# UMN_HASP_2015_HVPS.net
KiCad netlist of a schematic drawn in EAGLE
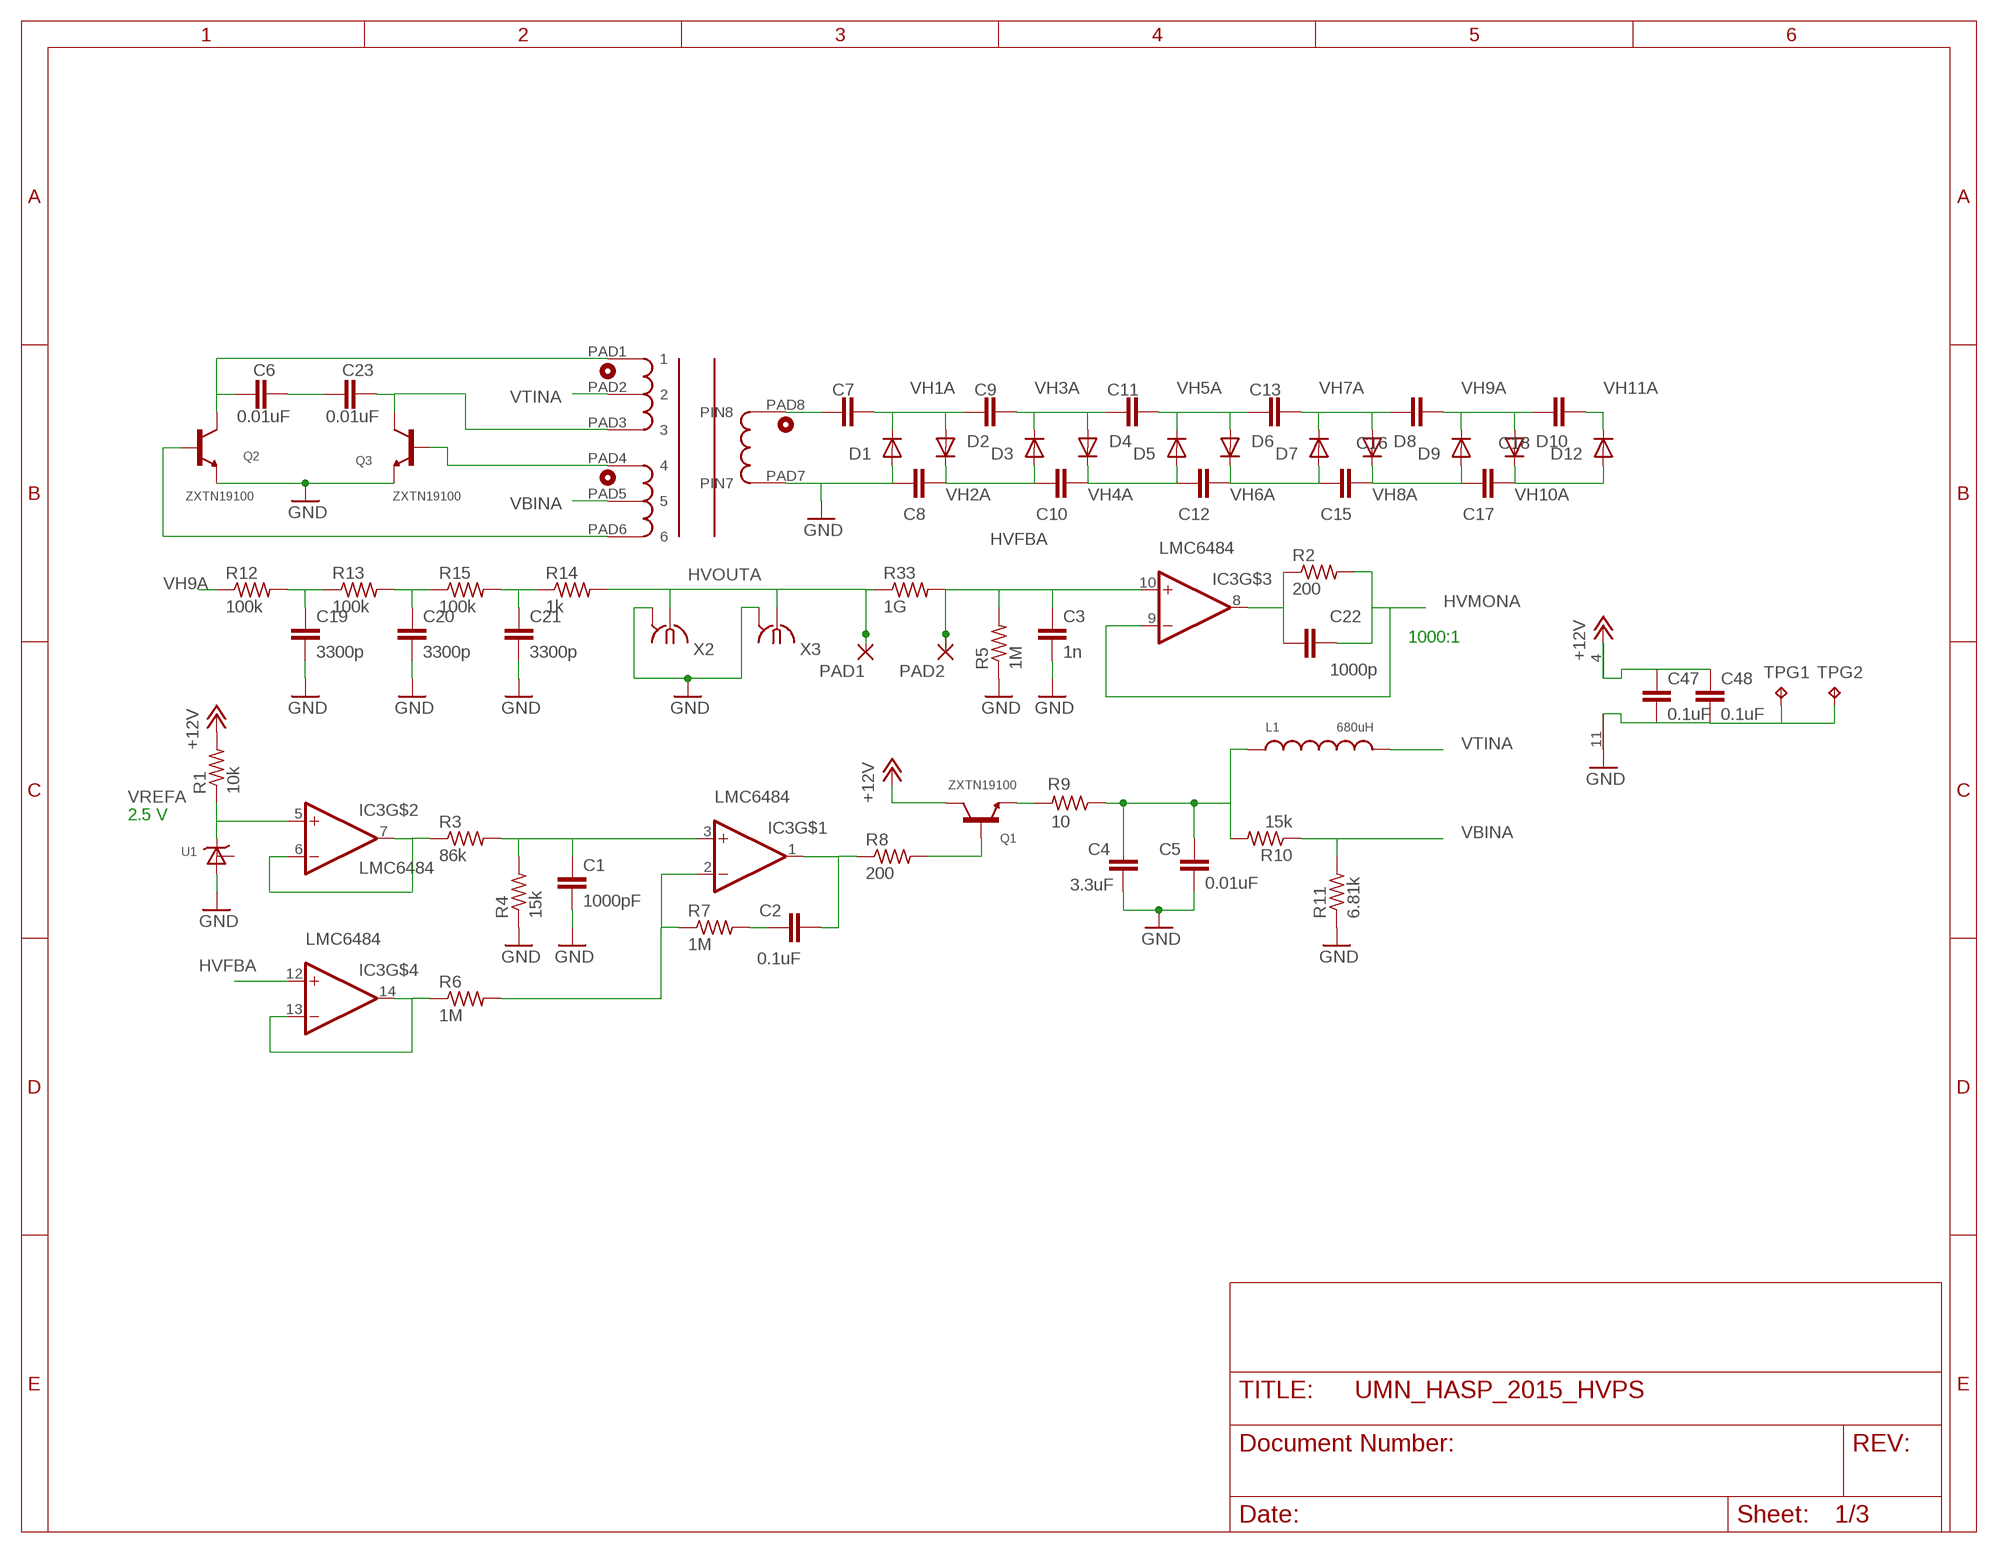
[diagram p0: schematic, sheet 1]
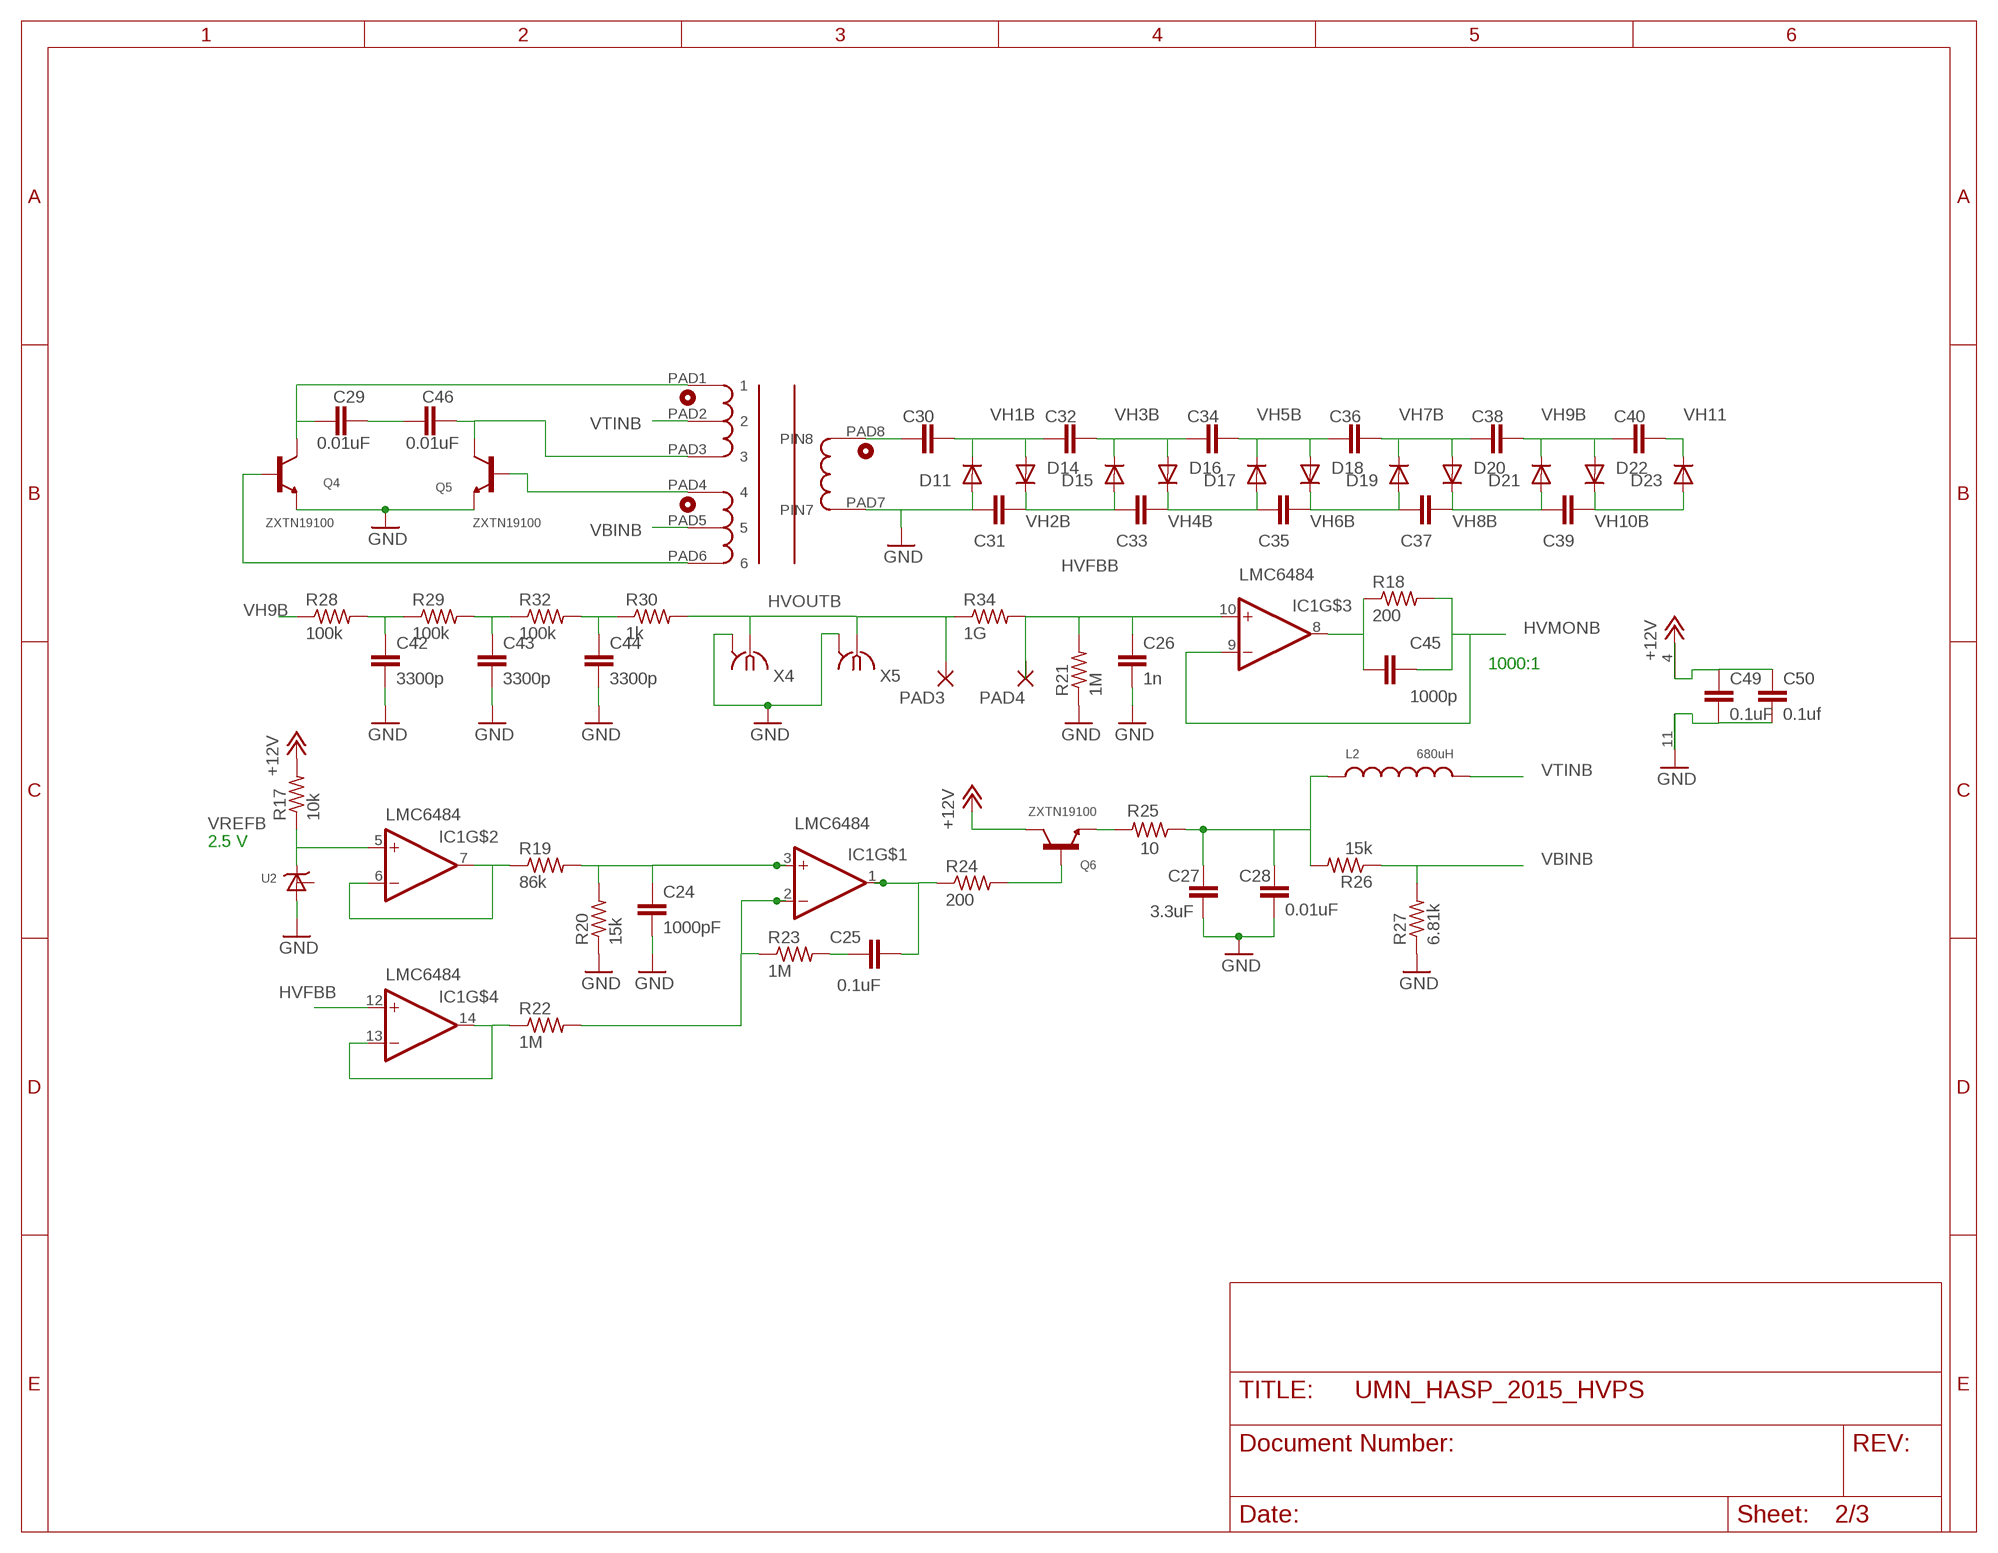
[diagram p1: schematic, sheet 2]
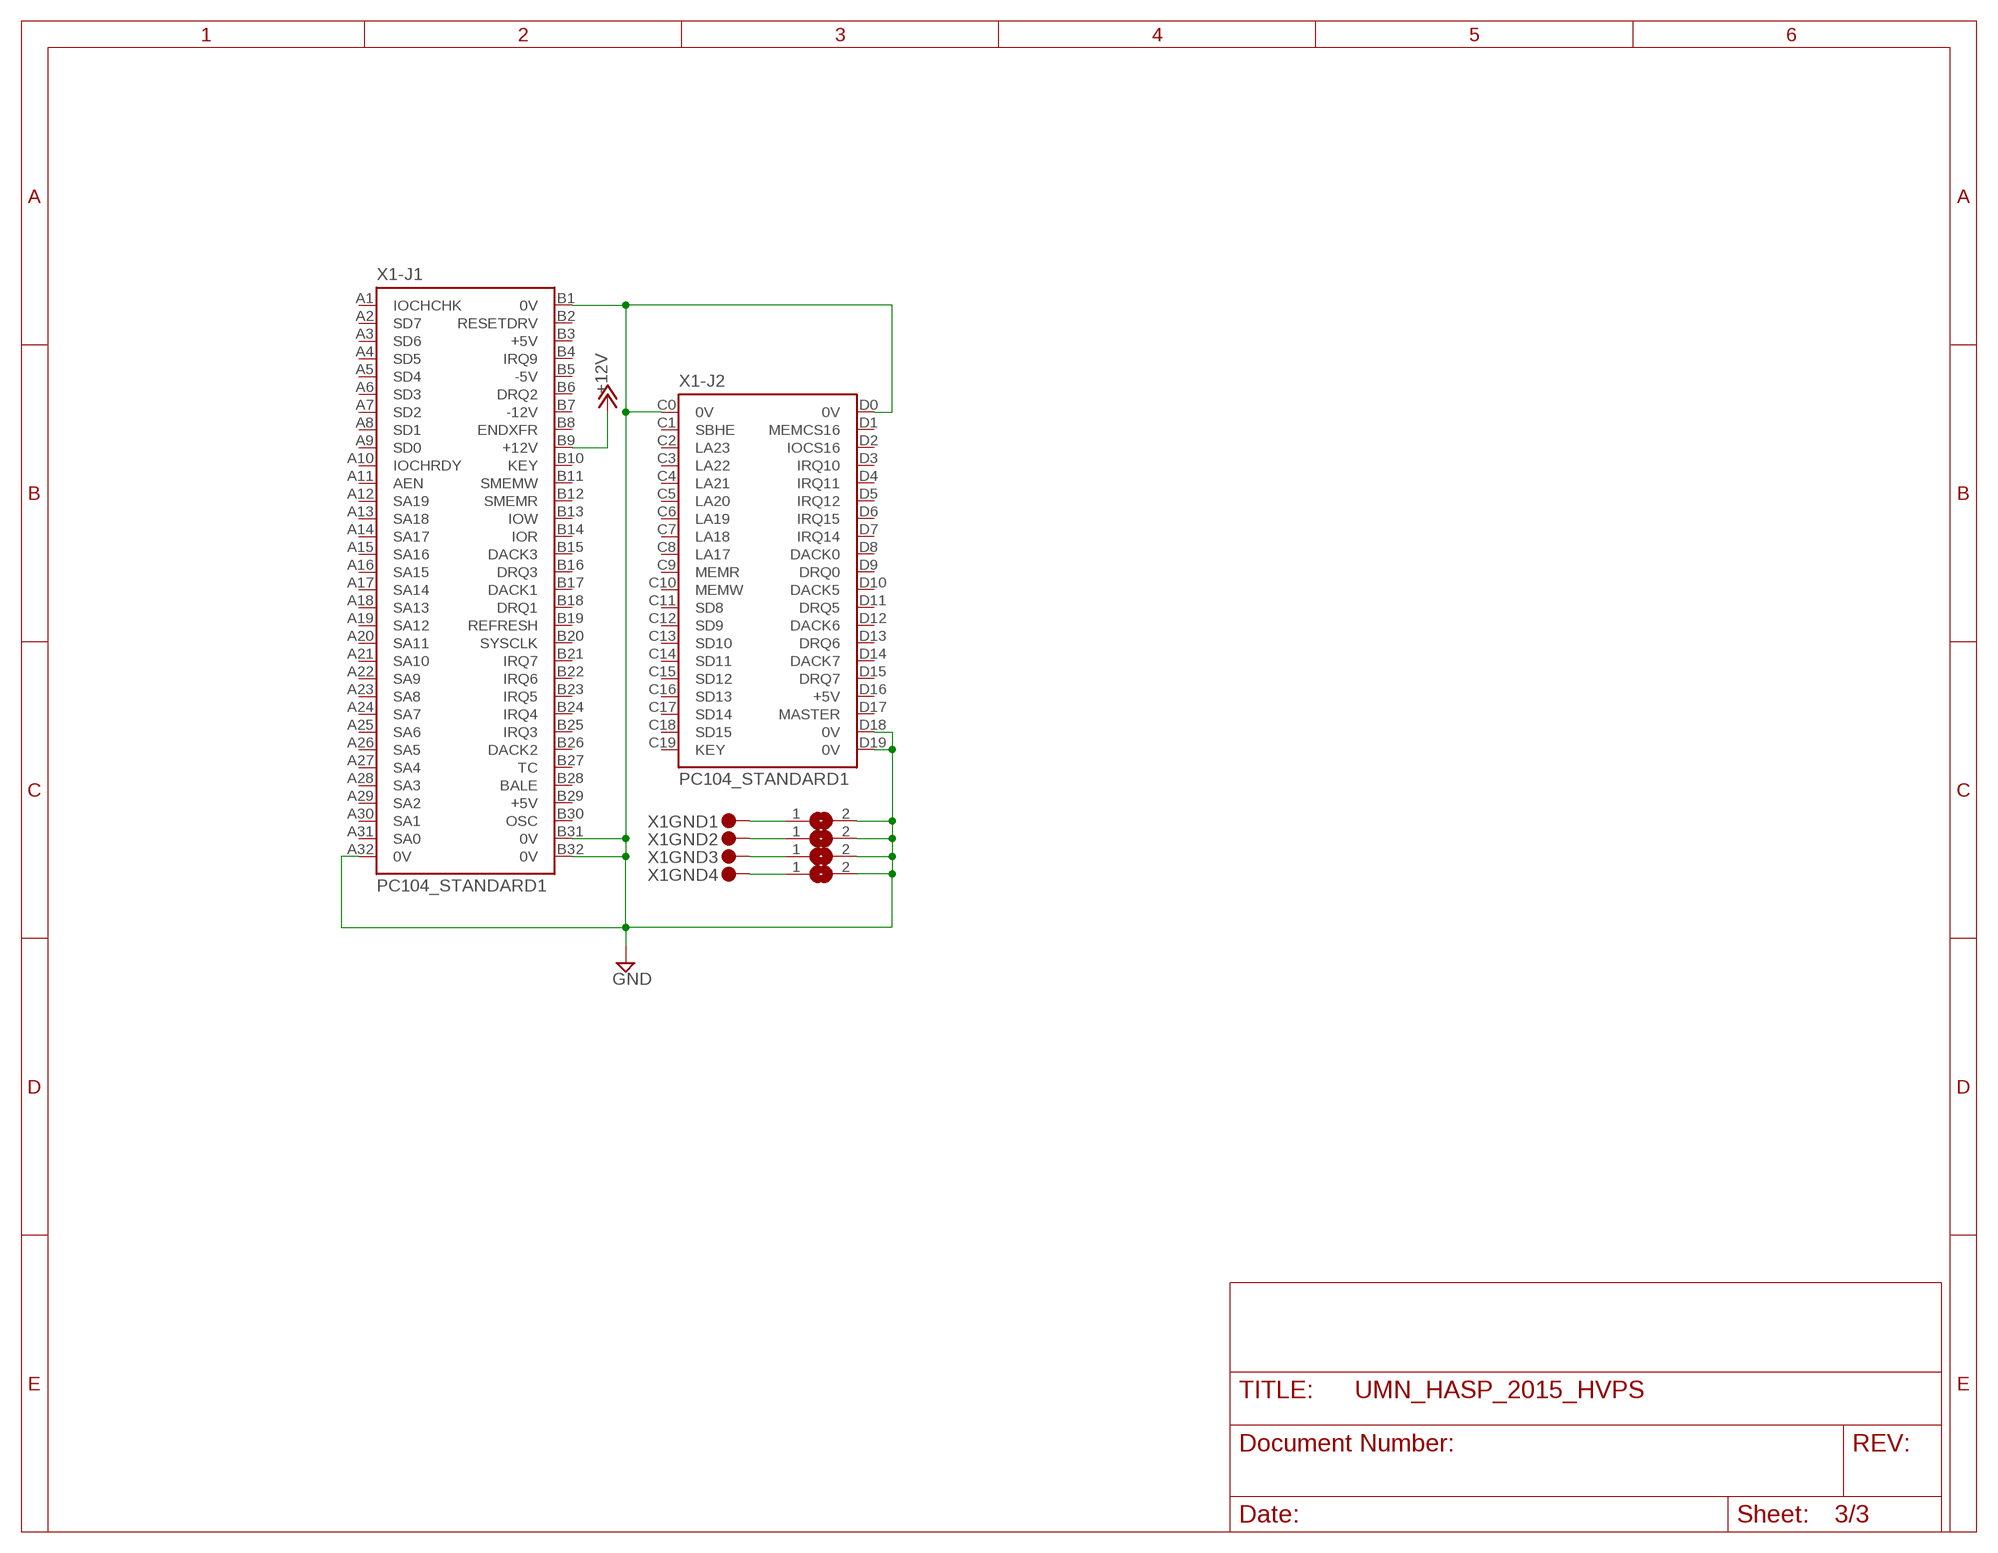
[diagram p2: schematic, sheet 3]

(export (version "E")
  (design (tool "Eeschema 10.0.6"))
  (components
    (comp (ref "SJ1") (value "SJ") (footprint "eagle-import:SJ") (libsource (lib "eagle-import") (part "SJ")))
    (comp (ref "SJ2") (value "SJ") (footprint "eagle-import:SJ") (libsource (lib "eagle-import") (part "SJ")))
    (comp (ref "SJ3") (value "SJ") (footprint "eagle-import:SJ") (libsource (lib "eagle-import") (part "SJ")))
    (comp (ref "SJ4") (value "SJ") (footprint "eagle-import:SJ") (libsource (lib "eagle-import") (part "SJ")))
    (comp (ref "X1")
      (value "PC104_STANDARD1")
      (footprint "eagle-import:PC104-STANDARD")
      (libsource (lib "eagle-import") (part "PC104_STANDARD1"))
    )
    (comp (ref "C1")
      (value "1000pF")
      (footprint "eagle-import:C0603")
      (libsource (lib "eagle-import") (part "C-EUC0603"))
    )
    (comp (ref "C2")
      (value "0.1uF")
      (footprint "eagle-import:C0603")
      (libsource (lib "eagle-import") (part "C-EUC0603"))
    )
    (comp (ref "C3")
      (value "1n")
      (footprint "eagle-import:C0603")
      (libsource (lib "eagle-import") (part "C-EUC0603"))
    )
    (comp (ref "C4")
      (value "3.3uF")
      (footprint "eagle-import:C0603")
      (libsource (lib "eagle-import") (part "C-EUC0603"))
    )
    (comp (ref "C5")
      (value "0.01uF")
      (footprint "eagle-import:C0603")
      (libsource (lib "eagle-import") (part "C-EUC0603"))
    )
    (comp (ref "C6")
      (value "0.01uF")
      (footprint "eagle-import:C0603")
      (libsource (lib "eagle-import") (part "C-EUC0603"))
    )
    (comp (ref "C7")
      (value "C-EUC1206K")
      (footprint "eagle-import:C1206K")
      (libsource (lib "eagle-import") (part "C-EUC1206K"))
    )
    (comp (ref "C8")
      (value "C-EUC1206K")
      (footprint "eagle-import:C1206K")
      (libsource (lib "eagle-import") (part "C-EUC1206K"))
    )
    (comp (ref "C9")
      (value "C-EUC1206K")
      (footprint "eagle-import:C1206K")
      (libsource (lib "eagle-import") (part "C-EUC1206K"))
    )
    (comp (ref "C10")
      (value "C-EUC1206K")
      (footprint "eagle-import:C1206K")
      (libsource (lib "eagle-import") (part "C-EUC1206K"))
    )
    (comp (ref "C11")
      (value "C-EUC1206K")
      (footprint "eagle-import:C1206K")
      (libsource (lib "eagle-import") (part "C-EUC1206K"))
    )
    (comp (ref "C12")
      (value "C-EUC1206K")
      (footprint "eagle-import:C1206K")
      (libsource (lib "eagle-import") (part "C-EUC1206K"))
    )
    (comp (ref "C13")
      (value "C-EUC1206K")
      (footprint "eagle-import:C1206K")
      (libsource (lib "eagle-import") (part "C-EUC1206K"))
    )
    (comp (ref "C15")
      (value "C-EUC1206K")
      (footprint "eagle-import:C1206K")
      (libsource (lib "eagle-import") (part "C-EUC1206K"))
    )
    (comp (ref "C16")
      (value "C-EUC1206K")
      (footprint "eagle-import:C1206K")
      (libsource (lib "eagle-import") (part "C-EUC1206K"))
    )
    (comp (ref "C17")
      (value "C-EUC1206K")
      (footprint "eagle-import:C1206K")
      (libsource (lib "eagle-import") (part "C-EUC1206K"))
    )
    (comp (ref "C18")
      (value "C-EUC1206K")
      (footprint "eagle-import:C1206K")
      (libsource (lib "eagle-import") (part "C-EUC1206K"))
    )
    (comp (ref "C19")
      (value "3300p")
      (footprint "eagle-import:C1206")
      (libsource (lib "eagle-import") (part "C-EUC1206"))
    )
    (comp (ref "C20")
      (value "3300p")
      (footprint "eagle-import:C1206")
      (libsource (lib "eagle-import") (part "C-EUC1206"))
    )
    (comp (ref "C21")
      (value "3300p")
      (footprint "eagle-import:C1206")
      (libsource (lib "eagle-import") (part "C-EUC1206"))
    )
    (comp (ref "C22")
      (value "1000p")
      (footprint "eagle-import:C0603")
      (libsource (lib "eagle-import") (part "C-EUC0603"))
    )
    (comp (ref "C23")
      (value "0.01uF")
      (footprint "eagle-import:C0603")
      (libsource (lib "eagle-import") (part "C-EUC0603"))
    )
    (comp (ref "C47")
      (value "0.1uF")
      (footprint "eagle-import:C0603")
      (libsource (lib "eagle-import") (part "C-EUC0603"))
    )
    (comp (ref "C48")
      (value "0.1uF")
      (footprint "eagle-import:C0603")
      (libsource (lib "eagle-import") (part "C-EUC0603"))
    )
    (comp (ref "D1")
      (value "DIODE-DO-214AC")
      (footprint "eagle-import:DO-214AC")
      (libsource (lib "eagle-import") (part "DIODE-DO-214AC"))
    )
    (comp (ref "D2")
      (value "DIODE-DO-214AC")
      (footprint "eagle-import:DO-214AC")
      (libsource (lib "eagle-import") (part "DIODE-DO-214AC"))
    )
    (comp (ref "D3")
      (value "DIODE-DO-214AC")
      (footprint "eagle-import:DO-214AC")
      (libsource (lib "eagle-import") (part "DIODE-DO-214AC"))
    )
    (comp (ref "D4")
      (value "DIODE-DO-214AC")
      (footprint "eagle-import:DO-214AC")
      (libsource (lib "eagle-import") (part "DIODE-DO-214AC"))
    )
    (comp (ref "D5")
      (value "DIODE-DO-214AC")
      (footprint "eagle-import:DO-214AC")
      (libsource (lib "eagle-import") (part "DIODE-DO-214AC"))
    )
    (comp (ref "D6")
      (value "DIODE-DO-214AC")
      (footprint "eagle-import:DO-214AC")
      (libsource (lib "eagle-import") (part "DIODE-DO-214AC"))
    )
    (comp (ref "D7")
      (value "DIODE-DO-214AC")
      (footprint "eagle-import:DO-214AC")
      (libsource (lib "eagle-import") (part "DIODE-DO-214AC"))
    )
    (comp (ref "D8")
      (value "DIODE-DO-214AC")
      (footprint "eagle-import:DO-214AC")
      (libsource (lib "eagle-import") (part "DIODE-DO-214AC"))
    )
    (comp (ref "D9")
      (value "DIODE-DO-214AC")
      (footprint "eagle-import:DO-214AC")
      (libsource (lib "eagle-import") (part "DIODE-DO-214AC"))
    )
    (comp (ref "D10")
      (value "DIODE-DO-214AC")
      (footprint "eagle-import:DO-214AC")
      (libsource (lib "eagle-import") (part "DIODE-DO-214AC"))
    )
    (comp (ref "D12")
      (value "DIODE-DO-214AC")
      (footprint "eagle-import:DO-214AC")
      (libsource (lib "eagle-import") (part "DIODE-DO-214AC"))
    )
    (comp (ref "IC3")
      (value "LMC6484")
      (footprint "eagle-import:SO14")
      (libsource (lib "eagle-import") (part "LMC6484"))
    )
    (comp (ref "L1")
      (value "680uH")
      (footprint "eagle-import:INDUCTOR_SRR1280BOURNS")
      (libsource (lib "eagle-import") (part "INDUCTOR_BOURNS_SRR1280_SERIES"))
    )
    (comp (ref "PAD1")
      (value "WIREPADSMD1,27-254")
      (footprint "eagle-import:SMD1,27-2,54")
      (libsource (lib "eagle-import") (part "WIREPADSMD1,27-254"))
    )
    (comp (ref "PAD2")
      (value "WIREPADSMD1,27-254")
      (footprint "eagle-import:SMD1,27-2,54")
      (libsource (lib "eagle-import") (part "WIREPADSMD1,27-254"))
    )
    (comp (ref "Q1")
      (value "ZXTN19100")
      (footprint "eagle-import:SOT23_2CM_SQ_AREA")
      (libsource (lib "eagle-import") (part "ZXTN19100_NPN"))
    )
    (comp (ref "Q2")
      (value "ZXTN19100")
      (footprint "eagle-import:SOT23_2CM_SQ_AREA")
      (libsource (lib "eagle-import") (part "ZXTN19100_NPN"))
    )
    (comp (ref "Q3")
      (value "ZXTN19100")
      (footprint "eagle-import:SOT23_2CM_SQ_AREA")
      (libsource (lib "eagle-import") (part "ZXTN19100_NPN"))
    )
    (comp (ref "R1")
      (value "10k")
      (footprint "eagle-import:R0603")
      (libsource (lib "eagle-import") (part "R-US_R0603"))
    )
    (comp (ref "R2")
      (value "200")
      (footprint "eagle-import:R0603")
      (libsource (lib "eagle-import") (part "R-US_R0603"))
    )
    (comp (ref "R3")
      (value "86k")
      (footprint "eagle-import:R0603")
      (libsource (lib "eagle-import") (part "R-US_R0603"))
    )
    (comp (ref "R4")
      (value "15k")
      (footprint "eagle-import:R0603")
      (libsource (lib "eagle-import") (part "R-US_R0603"))
    )
    (comp (ref "R5")
      (value "1M")
      (footprint "eagle-import:R0603")
      (libsource (lib "eagle-import") (part "R-US_R0603"))
    )
    (comp (ref "R6")
      (value "1M")
      (footprint "eagle-import:R0603")
      (libsource (lib "eagle-import") (part "R-US_R0603"))
    )
    (comp (ref "R7")
      (value "1M")
      (footprint "eagle-import:R0603")
      (libsource (lib "eagle-import") (part "R-US_R0603"))
    )
    (comp (ref "R8")
      (value "200")
      (footprint "eagle-import:R0603")
      (libsource (lib "eagle-import") (part "R-US_R0603"))
    )
    (comp (ref "R9")
      (value "10")
      (footprint "eagle-import:R2010")
      (libsource (lib "eagle-import") (part "R-US_R2010"))
    )
    (comp (ref "R10")
      (value "15k")
      (footprint "eagle-import:R0603")
      (libsource (lib "eagle-import") (part "R-US_R0603"))
    )
    (comp (ref "R11")
      (value "6.81k")
      (footprint "eagle-import:R0603")
      (libsource (lib "eagle-import") (part "R-US_R0603"))
    )
    (comp (ref "R12")
      (value "100k")
      (footprint "eagle-import:R0603")
      (libsource (lib "eagle-import") (part "R-US_R0603"))
    )
    (comp (ref "R13")
      (value "100k")
      (footprint "eagle-import:R0603")
      (libsource (lib "eagle-import") (part "R-US_R0603"))
    )
    (comp (ref "R14")
      (value "1k")
      (footprint "eagle-import:R0603")
      (libsource (lib "eagle-import") (part "R-US_R0603"))
    )
    (comp (ref "R15")
      (value "100k")
      (footprint "eagle-import:R0603")
      (libsource (lib "eagle-import") (part "R-US_R0603"))
    )
    (comp (ref "R33")
      (value "1G")
      (footprint "eagle-import:R2512")
      (libsource (lib "eagle-import") (part "R-US_R2512"))
    )
    (comp (ref "TPG1")
      (value "TPB1,27")
      (footprint "eagle-import:B1,27")
      (libsource (lib "eagle-import") (part "TPB1,27"))
    )
    (comp (ref "TPG2")
      (value "TPB1,27")
      (footprint "eagle-import:B1,27")
      (libsource (lib "eagle-import") (part "TPB1,27"))
    )
    (comp (ref "U$1")
      (value "TDK_TRANSFORMER_RM6_CORE")
      (footprint "eagle-import:SM_DCOILFORMER_RM6")
      (libsource (lib "eagle-import") (part "TDK_TRANSFORMER_RM6_CORE"))
    )
    (comp (ref "U1")
      (value "ADR525")
      (footprint "eagle-import:SOT23A")
      (libsource (lib "eagle-import") (part "ADR525"))
    )
    (comp (ref "X2")
      (value "BU-SMA-V-REVB")
      (footprint "eagle-import:BU-SMA-V")
      (libsource (lib "eagle-import") (part "BU-SMA-V-REVB"))
    )
    (comp (ref "X3")
      (value "BU-SMA-V-REVB")
      (footprint "eagle-import:BU-SMA-V")
      (libsource (lib "eagle-import") (part "BU-SMA-V-REVB"))
    )
    (comp (ref "C24")
      (value "1000pF")
      (footprint "eagle-import:C0603")
      (libsource (lib "eagle-import") (part "C-EUC0603"))
    )
    (comp (ref "C25")
      (value "0.1uF")
      (footprint "eagle-import:C0603")
      (libsource (lib "eagle-import") (part "C-EUC0603"))
    )
    (comp (ref "C26")
      (value "1n")
      (footprint "eagle-import:C0603")
      (libsource (lib "eagle-import") (part "C-EUC0603"))
    )
    (comp (ref "C27")
      (value "3.3uF")
      (footprint "eagle-import:C0603")
      (libsource (lib "eagle-import") (part "C-EUC0603"))
    )
    (comp (ref "C28")
      (value "0.01uF")
      (footprint "eagle-import:C0603")
      (libsource (lib "eagle-import") (part "C-EUC0603"))
    )
    (comp (ref "C29")
      (value "0.01uF")
      (footprint "eagle-import:C0603")
      (libsource (lib "eagle-import") (part "C-EUC0603"))
    )
    (comp (ref "C30")
      (value "C-EUC1206K")
      (footprint "eagle-import:C1206K")
      (libsource (lib "eagle-import") (part "C-EUC1206K"))
    )
    (comp (ref "C31")
      (value "C-EUC1206K")
      (footprint "eagle-import:C1206K")
      (libsource (lib "eagle-import") (part "C-EUC1206K"))
    )
    (comp (ref "C32")
      (value "C-EUC1206K")
      (footprint "eagle-import:C1206K")
      (libsource (lib "eagle-import") (part "C-EUC1206K"))
    )
    (comp (ref "C33")
      (value "C-EUC1206K")
      (footprint "eagle-import:C1206K")
      (libsource (lib "eagle-import") (part "C-EUC1206K"))
    )
    (comp (ref "C34")
      (value "C-EUC1206K")
      (footprint "eagle-import:C1206K")
      (libsource (lib "eagle-import") (part "C-EUC1206K"))
    )
    (comp (ref "C35")
      (value "C-EUC1206K")
      (footprint "eagle-import:C1206K")
      (libsource (lib "eagle-import") (part "C-EUC1206K"))
    )
    (comp (ref "C36")
      (value "C-EUC1206K")
      (footprint "eagle-import:C1206K")
      (libsource (lib "eagle-import") (part "C-EUC1206K"))
    )
    (comp (ref "C37")
      (value "C-EUC1206K")
      (footprint "eagle-import:C1206K")
      (libsource (lib "eagle-import") (part "C-EUC1206K"))
    )
    (comp (ref "C38")
      (value "C-EUC1206K")
      (footprint "eagle-import:C1206K")
      (libsource (lib "eagle-import") (part "C-EUC1206K"))
    )
    (comp (ref "C39")
      (value "C-EUC1206K")
      (footprint "eagle-import:C1206K")
      (libsource (lib "eagle-import") (part "C-EUC1206K"))
    )
    (comp (ref "C40")
      (value "C-EUC1206K")
      (footprint "eagle-import:C1206K")
      (libsource (lib "eagle-import") (part "C-EUC1206K"))
    )
    (comp (ref "C42")
      (value "3300p")
      (footprint "eagle-import:C1206")
      (libsource (lib "eagle-import") (part "C-EUC1206"))
    )
    (comp (ref "C43")
      (value "3300p")
      (footprint "eagle-import:C1206")
      (libsource (lib "eagle-import") (part "C-EUC1206"))
    )
    (comp (ref "C44")
      (value "3300p")
      (footprint "eagle-import:C1206")
      (libsource (lib "eagle-import") (part "C-EUC1206"))
    )
    (comp (ref "C45")
      (value "1000p")
      (footprint "eagle-import:C0603")
      (libsource (lib "eagle-import") (part "C-EUC0603"))
    )
    (comp (ref "C46")
      (value "0.01uF")
      (footprint "eagle-import:C0603")
      (libsource (lib "eagle-import") (part "C-EUC0603"))
    )
    (comp (ref "C49")
      (value "0.1uF")
      (footprint "eagle-import:C0603")
      (libsource (lib "eagle-import") (part "C-EUC0603"))
    )
    (comp (ref "C50")
      (value "0.1uf")
      (footprint "eagle-import:C0603")
      (libsource (lib "eagle-import") (part "C-EUC0603"))
    )
    (comp (ref "D11")
      (value "DIODE-DO-214AC")
      (footprint "eagle-import:DO-214AC")
      (libsource (lib "eagle-import") (part "DIODE-DO-214AC"))
    )
    (comp (ref "D14")
      (value "DIODE-DO-214AC")
      (footprint "eagle-import:DO-214AC")
      (libsource (lib "eagle-import") (part "DIODE-DO-214AC"))
    )
    (comp (ref "D15")
      (value "DIODE-DO-214AC")
      (footprint "eagle-import:DO-214AC")
      (libsource (lib "eagle-import") (part "DIODE-DO-214AC"))
    )
    (comp (ref "D16")
      (value "DIODE-DO-214AC")
      (footprint "eagle-import:DO-214AC")
      (libsource (lib "eagle-import") (part "DIODE-DO-214AC"))
    )
    (comp (ref "D17")
      (value "DIODE-DO-214AC")
      (footprint "eagle-import:DO-214AC")
      (libsource (lib "eagle-import") (part "DIODE-DO-214AC"))
    )
    (comp (ref "D18")
      (value "DIODE-DO-214AC")
      (footprint "eagle-import:DO-214AC")
      (libsource (lib "eagle-import") (part "DIODE-DO-214AC"))
    )
    (comp (ref "D19")
      (value "DIODE-DO-214AC")
      (footprint "eagle-import:DO-214AC")
      (libsource (lib "eagle-import") (part "DIODE-DO-214AC"))
    )
    (comp (ref "D20")
      (value "DIODE-DO-214AC")
      (footprint "eagle-import:DO-214AC")
      (libsource (lib "eagle-import") (part "DIODE-DO-214AC"))
    )
    (comp (ref "D21")
      (value "DIODE-DO-214AC")
      (footprint "eagle-import:DO-214AC")
      (libsource (lib "eagle-import") (part "DIODE-DO-214AC"))
    )
    (comp (ref "D22")
      (value "DIODE-DO-214AC")
      (footprint "eagle-import:DO-214AC")
      (libsource (lib "eagle-import") (part "DIODE-DO-214AC"))
    )
    (comp (ref "D23")
      (value "DIODE-DO-214AC")
      (footprint "eagle-import:DO-214AC")
      (libsource (lib "eagle-import") (part "DIODE-DO-214AC"))
    )
    (comp (ref "IC1")
      (value "LMC6484")
      (footprint "eagle-import:SO14")
      (libsource (lib "eagle-import") (part "LMC6484"))
    )
    (comp (ref "L2")
      (value "680uH")
      (footprint "eagle-import:INDUCTOR_SRR1280BOURNS")
      (libsource (lib "eagle-import") (part "INDUCTOR_BOURNS_SRR1280_SERIES"))
    )
    (comp (ref "PAD3")
      (value "WIREPADSMD1,27-254")
      (footprint "eagle-import:SMD1,27-2,54")
      (libsource (lib "eagle-import") (part "WIREPADSMD1,27-254"))
    )
    (comp (ref "PAD4")
      (value "WIREPADSMD1,27-254")
      (footprint "eagle-import:SMD1,27-2,54")
      (libsource (lib "eagle-import") (part "WIREPADSMD1,27-254"))
    )
    (comp (ref "Q4")
      (value "ZXTN19100")
      (footprint "eagle-import:SOT23_2CM_SQ_AREA")
      (libsource (lib "eagle-import") (part "ZXTN19100_NPN"))
    )
    (comp (ref "Q5")
      (value "ZXTN19100")
      (footprint "eagle-import:SOT23_2CM_SQ_AREA")
      (libsource (lib "eagle-import") (part "ZXTN19100_NPN"))
    )
    (comp (ref "Q6")
      (value "ZXTN19100")
      (footprint "eagle-import:SOT23_2CM_SQ_AREA")
      (libsource (lib "eagle-import") (part "ZXTN19100_NPN"))
    )
    (comp (ref "R17")
      (value "10k")
      (footprint "eagle-import:R0603")
      (libsource (lib "eagle-import") (part "R-US_R0603"))
    )
    (comp (ref "R18")
      (value "200")
      (footprint "eagle-import:R0603")
      (libsource (lib "eagle-import") (part "R-US_R0603"))
    )
    (comp (ref "R19")
      (value "86k")
      (footprint "eagle-import:R0603")
      (libsource (lib "eagle-import") (part "R-US_R0603"))
    )
    (comp (ref "R20")
      (value "15k")
      (footprint "eagle-import:R0603")
      (libsource (lib "eagle-import") (part "R-US_R0603"))
    )
    (comp (ref "R21")
      (value "1M")
      (footprint "eagle-import:R0603")
      (libsource (lib "eagle-import") (part "R-US_R0603"))
    )
    (comp (ref "R22")
      (value "1M")
      (footprint "eagle-import:R0603")
      (libsource (lib "eagle-import") (part "R-US_R0603"))
    )
    (comp (ref "R23")
      (value "1M")
      (footprint "eagle-import:R0603")
      (libsource (lib "eagle-import") (part "R-US_R0603"))
    )
    (comp (ref "R24")
      (value "200")
      (footprint "eagle-import:R0603")
      (libsource (lib "eagle-import") (part "R-US_R0603"))
    )
    (comp (ref "R25")
      (value "10")
      (footprint "eagle-import:R2010")
      (libsource (lib "eagle-import") (part "R-US_R2010"))
    )
    (comp (ref "R26")
      (value "15k")
      (footprint "eagle-import:R0603")
      (libsource (lib "eagle-import") (part "R-US_R0603"))
    )
    (comp (ref "R27")
      (value "6.81k")
      (footprint "eagle-import:R0603")
      (libsource (lib "eagle-import") (part "R-US_R0603"))
    )
    (comp (ref "R28")
      (value "100k")
      (footprint "eagle-import:R0603")
      (libsource (lib "eagle-import") (part "R-US_R0603"))
    )
    (comp (ref "R29")
      (value "100k")
      (footprint "eagle-import:R0603")
      (libsource (lib "eagle-import") (part "R-US_R0603"))
    )
    (comp (ref "R30")
      (value "1k")
      (footprint "eagle-import:R0603")
      (libsource (lib "eagle-import") (part "R-US_R0603"))
    )
    (comp (ref "R32")
      (value "100k")
      (footprint "eagle-import:R0603")
      (libsource (lib "eagle-import") (part "R-US_R0603"))
    )
    (comp (ref "R34")
      (value "1G")
      (footprint "eagle-import:R2512")
      (libsource (lib "eagle-import") (part "R-US_R2512"))
    )
    (comp (ref "U$2")
      (value "TDK_TRANSFORMER_RM6_CORE")
      (footprint "eagle-import:SM_DCOILFORMER_RM6")
      (libsource (lib "eagle-import") (part "TDK_TRANSFORMER_RM6_CORE"))
    )
    (comp (ref "U2")
      (value "ADR525")
      (footprint "eagle-import:SOT23A")
      (libsource (lib "eagle-import") (part "ADR525"))
    )
    (comp (ref "X4")
      (value "BU-SMA-V-REVB")
      (footprint "eagle-import:BU-SMA-V")
      (libsource (lib "eagle-import") (part "BU-SMA-V-REVB"))
    )
    (comp (ref "X5")
      (value "BU-SMA-V-REVB")
      (footprint "eagle-import:BU-SMA-V")
      (libsource (lib "eagle-import") (part "BU-SMA-V-REVB"))
    )
  )
  (nets
    (net (code "1") (name "+12V") (class "Default")
      (node (ref "C47") (pin "1") (pinfunction "1_1") (pintype "passive"))
      (node (ref "C48") (pin "1") (pinfunction "1_1") (pintype "passive"))
      (node (ref "C49") (pin "1") (pinfunction "1_1") (pintype "passive"))
      (node (ref "C50") (pin "1") (pinfunction "1_1") (pintype "passive"))
      (node (ref "IC1") (pin "4") (pinfunction "V+_4") (pintype "power_in"))
      (node (ref "IC3") (pin "4") (pinfunction "V+_4") (pintype "power_in"))
      (node (ref "Q1") (pin "C") (pinfunction "C_C") (pintype "passive"))
      (node (ref "Q6") (pin "C") (pinfunction "C_C") (pintype "passive"))
      (node (ref "R1") (pin "2") (pinfunction "2_2") (pintype "passive"))
      (node (ref "R17") (pin "2") (pinfunction "2_2") (pintype "passive"))
      (node (ref "X1") (pin "B9") (pinfunction "+12V_B9") (pintype "passive"))
    )
    (net (code "2") (name "GND") (class "Default")
      (node (ref "C1") (pin "2") (pinfunction "2_2") (pintype "passive"))
      (node (ref "C19") (pin "2") (pinfunction "2_2") (pintype "passive"))
      (node (ref "C20") (pin "2") (pinfunction "2_2") (pintype "passive"))
      (node (ref "C21") (pin "2") (pinfunction "2_2") (pintype "passive"))
      (node (ref "C24") (pin "2") (pinfunction "2_2") (pintype "passive"))
      (node (ref "C26") (pin "2") (pinfunction "2_2") (pintype "passive"))
      (node (ref "C27") (pin "2") (pinfunction "2_2") (pintype "passive"))
      (node (ref "C28") (pin "2") (pinfunction "2_2") (pintype "passive"))
      (node (ref "C3") (pin "2") (pinfunction "2_2") (pintype "passive"))
      (node (ref "C31") (pin "1") (pinfunction "1_1") (pintype "passive"))
      (node (ref "C4") (pin "2") (pinfunction "2_2") (pintype "passive"))
      (node (ref "C42") (pin "2") (pinfunction "2_2") (pintype "passive"))
      (node (ref "C43") (pin "2") (pinfunction "2_2") (pintype "passive"))
      (node (ref "C44") (pin "2") (pinfunction "2_2") (pintype "passive"))
      (node (ref "C47") (pin "2") (pinfunction "2_2") (pintype "passive"))
      (node (ref "C48") (pin "2") (pinfunction "2_2") (pintype "passive"))
      (node (ref "C49") (pin "2") (pinfunction "2_2") (pintype "passive"))
      (node (ref "C5") (pin "2") (pinfunction "2_2") (pintype "passive"))
      (node (ref "C50") (pin "2") (pinfunction "2_2") (pintype "passive"))
      (node (ref "C8") (pin "1") (pinfunction "1_1") (pintype "passive"))
      (node (ref "D1") (pin "A") (pinfunction "A_A") (pintype "passive"))
      (node (ref "D11") (pin "A") (pinfunction "A_A") (pintype "passive"))
      (node (ref "IC1") (pin "11") (pinfunction "V-_11") (pintype "power_in"))
      (node (ref "IC3") (pin "11") (pinfunction "V-_11") (pintype "power_in"))
      (node (ref "Q2") (pin "E") (pinfunction "E_E") (pintype "passive"))
      (node (ref "Q3") (pin "E") (pinfunction "E_E") (pintype "passive"))
      (node (ref "Q4") (pin "E") (pinfunction "E_E") (pintype "passive"))
      (node (ref "Q5") (pin "E") (pinfunction "E_E") (pintype "passive"))
      (node (ref "R11") (pin "1") (pinfunction "1_1") (pintype "passive"))
      (node (ref "R20") (pin "1") (pinfunction "1_1") (pintype "passive"))
      (node (ref "R21") (pin "1") (pinfunction "1_1") (pintype "passive"))
      (node (ref "R27") (pin "1") (pinfunction "1_1") (pintype "passive"))
      (node (ref "R4") (pin "1") (pinfunction "1_1") (pintype "passive"))
      (node (ref "R5") (pin "1") (pinfunction "1_1") (pintype "passive"))
      (node (ref "SJ1") (pin "2") (pinfunction "2_2") (pintype "passive"))
      (node (ref "SJ2") (pin "2") (pinfunction "2_2") (pintype "passive"))
      (node (ref "SJ3") (pin "2") (pinfunction "2_2") (pintype "passive"))
      (node (ref "SJ4") (pin "2") (pinfunction "2_2") (pintype "passive"))
      (node (ref "TPG1") (pin "TP") (pinfunction "TP_TP") (pintype "input"))
      (node (ref "TPG2") (pin "TP") (pinfunction "TP_TP") (pintype "input"))
      (node (ref "U$1") (pin "PAD7") (pinfunction "PIN7_PAD7") (pintype "bidirectional"))
      (node (ref "U$2") (pin "PAD7") (pinfunction "PIN7_PAD7") (pintype "bidirectional"))
      (node (ref "U1") (pin "2") (pinfunction "V-_2") (pintype "bidirectional"))
      (node (ref "U2") (pin "2") (pinfunction "V-_2") (pintype "bidirectional"))
      (node (ref "X1") (pin "A32") (pinfunction "0V_A32") (pintype "passive"))
      (node (ref "X1") (pin "B1") (pinfunction "0V_B1") (pintype "passive"))
      (node (ref "X1") (pin "B31") (pinfunction "0V_B31") (pintype "passive"))
      (node (ref "X1") (pin "B32") (pinfunction "0V_B32") (pintype "passive"))
      (node (ref "X1") (pin "C0") (pinfunction "0V_C0") (pintype "passive"))
      (node (ref "X1") (pin "D0") (pinfunction "0V_D0") (pintype "passive"))
      (node (ref "X1") (pin "D18") (pinfunction "0V_D18") (pintype "passive"))
      (node (ref "X1") (pin "D19") (pinfunction "0V_D19") (pintype "passive"))
      (node (ref "X2") (pin "2") (pinfunction "GND_2") (pintype "power_in"))
      (node (ref "X3") (pin "2") (pinfunction "GND_2") (pintype "power_in"))
      (node (ref "X4") (pin "2") (pinfunction "GND_2") (pintype "power_in"))
      (node (ref "X5") (pin "2") (pinfunction "GND_2") (pintype "power_in"))
    )
    (net (code "3") (name "HVFBA") (class "Default")
      (node (ref "C3") (pin "1") (pinfunction "1_1") (pintype "passive"))
      (node (ref "IC3") (pin "10") (pinfunction "+IN_10") (pintype "input"))
      (node (ref "IC3") (pin "12") (pinfunction "+IN_12") (pintype "input"))
      (node (ref "PAD2") (pin "1") (pinfunction "P_1") (pintype "passive"))
      (node (ref "R33") (pin "2") (pinfunction "2_2") (pintype "passive"))
      (node (ref "R5") (pin "2") (pinfunction "2_2") (pintype "passive"))
    )
    (net (code "4") (name "HVFBB") (class "Default")
      (node (ref "C26") (pin "1") (pinfunction "1_1") (pintype "passive"))
      (node (ref "IC1") (pin "10") (pinfunction "+IN_10") (pintype "input"))
      (node (ref "IC1") (pin "12") (pinfunction "+IN_12") (pintype "input"))
      (node (ref "PAD4") (pin "1") (pinfunction "P_1") (pintype "passive"))
      (node (ref "R21") (pin "2") (pinfunction "2_2") (pintype "passive"))
      (node (ref "R34") (pin "2") (pinfunction "2_2") (pintype "passive"))
    )
    (net (code "5") (name "HVMONA") (class "Default")
      (node (ref "C22") (pin "1") (pinfunction "1_1") (pintype "passive"))
      (node (ref "IC3") (pin "9") (pinfunction "-IN_9") (pintype "input"))
      (node (ref "R2") (pin "2") (pinfunction "2_2") (pintype "passive"))
    )
    (net (code "6") (name "HVMONB") (class "Default")
      (node (ref "C45") (pin "1") (pinfunction "1_1") (pintype "passive"))
      (node (ref "IC1") (pin "9") (pinfunction "-IN_9") (pintype "input"))
      (node (ref "R18") (pin "2") (pinfunction "2_2") (pintype "passive"))
    )
    (net (code "7") (name "HVOUTA") (class "Default")
      (node (ref "PAD1") (pin "1") (pinfunction "P_1") (pintype "passive"))
      (node (ref "R14") (pin "2") (pinfunction "2_2") (pintype "passive"))
      (node (ref "R33") (pin "1") (pinfunction "1_1") (pintype "passive"))
      (node (ref "X2") (pin "1") (pinfunction "1_1") (pintype "passive"))
      (node (ref "X3") (pin "1") (pinfunction "1_1") (pintype "passive"))
    )
    (net (code "8") (name "HVOUTB") (class "Default")
      (node (ref "PAD3") (pin "1") (pinfunction "P_1") (pintype "passive"))
      (node (ref "R30") (pin "2") (pinfunction "2_2") (pintype "passive"))
      (node (ref "R34") (pin "1") (pinfunction "1_1") (pintype "passive"))
      (node (ref "X4") (pin "1") (pinfunction "1_1") (pintype "passive"))
      (node (ref "X5") (pin "1") (pinfunction "1_1") (pintype "passive"))
    )
    (net (code "9") (name "Net-(C2-Pad1)") (class "Default")
      (node (ref "C2") (pin "1") (pinfunction "1_1") (pintype "passive"))
      (node (ref "R7") (pin "2") (pinfunction "2_2") (pintype "passive"))
    )
    (net (code "10") (name "Net-(C4-Pad1)") (class "Default")
      (node (ref "C4") (pin "1") (pinfunction "1_1") (pintype "passive"))
      (node (ref "C5") (pin "1") (pinfunction "1_1") (pintype "passive"))
      (node (ref "L1") (pin "P$1") (pinfunction "P$1_P$1") (pintype "passive"))
      (node (ref "R10") (pin "2") (pinfunction "2_2") (pintype "passive"))
      (node (ref "R9") (pin "1") (pinfunction "1_1") (pintype "passive"))
    )
    (net (code "11") (name "Net-(C19-Pad1)") (class "Default")
      (node (ref "C19") (pin "1") (pinfunction "1_1") (pintype "passive"))
      (node (ref "R12") (pin "2") (pinfunction "2_2") (pintype "passive"))
      (node (ref "R13") (pin "1") (pinfunction "1_1") (pintype "passive"))
    )
    (net (code "12") (name "Net-(C20-Pad1)") (class "Default")
      (node (ref "C20") (pin "1") (pinfunction "1_1") (pintype "passive"))
      (node (ref "R13") (pin "2") (pinfunction "2_2") (pintype "passive"))
      (node (ref "R15") (pin "1") (pinfunction "1_1") (pintype "passive"))
    )
    (net (code "13") (name "Net-(C21-Pad1)") (class "Default")
      (node (ref "C21") (pin "1") (pinfunction "1_1") (pintype "passive"))
      (node (ref "R14") (pin "1") (pinfunction "1_1") (pintype "passive"))
      (node (ref "R15") (pin "2") (pinfunction "2_2") (pintype "passive"))
    )
    (net (code "14") (name "Net-(C23-Pad2)") (class "Default")
      (node (ref "C23") (pin "2") (pinfunction "2_2") (pintype "passive"))
      (node (ref "C6") (pin "1") (pinfunction "1_1") (pintype "passive"))
    )
    (net (code "15") (name "Net-(C25-Pad1)") (class "Default")
      (node (ref "C25") (pin "1") (pinfunction "1_1") (pintype "passive"))
      (node (ref "R23") (pin "2") (pinfunction "2_2") (pintype "passive"))
    )
    (net (code "16") (name "Net-(C27-Pad1)") (class "Default")
      (node (ref "C27") (pin "1") (pinfunction "1_1") (pintype "passive"))
      (node (ref "C28") (pin "1") (pinfunction "1_1") (pintype "passive"))
      (node (ref "L2") (pin "P$1") (pinfunction "P$1_P$1") (pintype "passive"))
      (node (ref "R25") (pin "1") (pinfunction "1_1") (pintype "passive"))
      (node (ref "R26") (pin "2") (pinfunction "2_2") (pintype "passive"))
    )
    (net (code "17") (name "Net-(C29-Pad1)") (class "Default")
      (node (ref "C29") (pin "1") (pinfunction "1_1") (pintype "passive"))
      (node (ref "C46") (pin "2") (pinfunction "2_2") (pintype "passive"))
    )
    (net (code "18") (name "Net-(C42-Pad1)") (class "Default")
      (node (ref "C42") (pin "1") (pinfunction "1_1") (pintype "passive"))
      (node (ref "R28") (pin "2") (pinfunction "2_2") (pintype "passive"))
      (node (ref "R29") (pin "1") (pinfunction "1_1") (pintype "passive"))
    )
    (net (code "19") (name "Net-(C43-Pad1)") (class "Default")
      (node (ref "C43") (pin "1") (pinfunction "1_1") (pintype "passive"))
      (node (ref "R29") (pin "2") (pinfunction "2_2") (pintype "passive"))
      (node (ref "R32") (pin "1") (pinfunction "1_1") (pintype "passive"))
    )
    (net (code "20") (name "Net-(C44-Pad1)") (class "Default")
      (node (ref "C44") (pin "1") (pinfunction "1_1") (pintype "passive"))
      (node (ref "R30") (pin "1") (pinfunction "1_1") (pintype "passive"))
      (node (ref "R32") (pin "2") (pinfunction "2_2") (pintype "passive"))
    )
    (net (code "21") (name "Net-(IC1A-+IN)") (class "Default")
      (node (ref "C24") (pin "1") (pinfunction "1_1") (pintype "passive"))
      (node (ref "IC1") (pin "3") (pinfunction "+IN_3") (pintype "input"))
      (node (ref "R19") (pin "2") (pinfunction "2_2") (pintype "passive"))
      (node (ref "R20") (pin "2") (pinfunction "2_2") (pintype "passive"))
    )
    (net (code "22") (name "Net-(IC1A--IN)") (class "Default")
      (node (ref "IC1") (pin "2") (pinfunction "-IN_2") (pintype "input"))
      (node (ref "R22") (pin "2") (pinfunction "2_2") (pintype "passive"))
      (node (ref "R23") (pin "1") (pinfunction "1_1") (pintype "passive"))
    )
    (net (code "23") (name "Net-(IC1A-OUT)") (class "Default")
      (node (ref "C25") (pin "2") (pinfunction "2_2") (pintype "passive"))
      (node (ref "IC1") (pin "1") (pinfunction "OUT_1") (pintype "output"))
      (node (ref "R24") (pin "1") (pinfunction "1_1") (pintype "passive"))
    )
    (net (code "24") (name "Net-(IC1B--IN)") (class "Default")
      (node (ref "IC1") (pin "6") (pinfunction "-IN_6") (pintype "input"))
      (node (ref "IC1") (pin "7") (pinfunction "OUT_7") (pintype "output"))
      (node (ref "R19") (pin "1") (pinfunction "1_1") (pintype "passive"))
    )
    (net (code "25") (name "Net-(IC1C-OUT)") (class "Default")
      (node (ref "C45") (pin "2") (pinfunction "2_2") (pintype "passive"))
      (node (ref "IC1") (pin "8") (pinfunction "OUT_8") (pintype "output"))
      (node (ref "R18") (pin "1") (pinfunction "1_1") (pintype "passive"))
    )
    (net (code "26") (name "Net-(IC1D--IN)") (class "Default")
      (node (ref "IC1") (pin "13") (pinfunction "-IN_13") (pintype "input"))
      (node (ref "IC1") (pin "14") (pinfunction "OUT_14") (pintype "output"))
      (node (ref "R22") (pin "1") (pinfunction "1_1") (pintype "passive"))
    )
    (net (code "27") (name "Net-(IC3A-+IN)") (class "Default")
      (node (ref "C1") (pin "1") (pinfunction "1_1") (pintype "passive"))
      (node (ref "IC3") (pin "3") (pinfunction "+IN_3") (pintype "input"))
      (node (ref "R3") (pin "2") (pinfunction "2_2") (pintype "passive"))
      (node (ref "R4") (pin "2") (pinfunction "2_2") (pintype "passive"))
    )
    (net (code "28") (name "Net-(IC3A--IN)") (class "Default")
      (node (ref "IC3") (pin "2") (pinfunction "-IN_2") (pintype "input"))
      (node (ref "R6") (pin "2") (pinfunction "2_2") (pintype "passive"))
      (node (ref "R7") (pin "1") (pinfunction "1_1") (pintype "passive"))
    )
    (net (code "29") (name "Net-(IC3A-OUT)") (class "Default")
      (node (ref "C2") (pin "2") (pinfunction "2_2") (pintype "passive"))
      (node (ref "IC3") (pin "1") (pinfunction "OUT_1") (pintype "output"))
      (node (ref "R8") (pin "1") (pinfunction "1_1") (pintype "passive"))
    )
    (net (code "30") (name "Net-(IC3B--IN)") (class "Default")
      (node (ref "IC3") (pin "6") (pinfunction "-IN_6") (pintype "input"))
      (node (ref "IC3") (pin "7") (pinfunction "OUT_7") (pintype "output"))
      (node (ref "R3") (pin "1") (pinfunction "1_1") (pintype "passive"))
    )
    (net (code "31") (name "Net-(IC3C-OUT)") (class "Default")
      (node (ref "C22") (pin "2") (pinfunction "2_2") (pintype "passive"))
      (node (ref "IC3") (pin "8") (pinfunction "OUT_8") (pintype "output"))
      (node (ref "R2") (pin "1") (pinfunction "1_1") (pintype "passive"))
    )
    (net (code "32") (name "Net-(IC3D--IN)") (class "Default")
      (node (ref "IC3") (pin "13") (pinfunction "-IN_13") (pintype "input"))
      (node (ref "IC3") (pin "14") (pinfunction "OUT_14") (pintype "output"))
      (node (ref "R6") (pin "1") (pinfunction "1_1") (pintype "passive"))
    )
    (net (code "33") (name "Net-(Q1-PadB)") (class "Default")
      (node (ref "Q1") (pin "B") (pinfunction "B_B") (pintype "passive"))
      (node (ref "R8") (pin "2") (pinfunction "2_2") (pintype "passive"))
    )
    (net (code "34") (name "Net-(Q1-PadE)") (class "Default")
      (node (ref "Q1") (pin "E") (pinfunction "E_E") (pintype "passive"))
      (node (ref "R9") (pin "2") (pinfunction "2_2") (pintype "passive"))
    )
    (net (code "35") (name "Net-(Q6-PadB)") (class "Default")
      (node (ref "Q6") (pin "B") (pinfunction "B_B") (pintype "passive"))
      (node (ref "R24") (pin "2") (pinfunction "2_2") (pintype "passive"))
    )
    (net (code "36") (name "Net-(Q6-PadE)") (class "Default")
      (node (ref "Q6") (pin "E") (pinfunction "E_E") (pintype "passive"))
      (node (ref "R25") (pin "2") (pinfunction "2_2") (pintype "passive"))
    )
    (net (code "37") (name "Net-(U$1-1)") (class "Default")
      (node (ref "C6") (pin "2") (pinfunction "2_2") (pintype "passive"))
      (node (ref "Q2") (pin "C") (pinfunction "C_C") (pintype "passive"))
      (node (ref "U$1") (pin "PAD1") (pinfunction "1_PAD1") (pintype "bidirectional"))
    )
    (net (code "38") (name "Net-(U$1-3)") (class "Default")
      (node (ref "C23") (pin "1") (pinfunction "1_1") (pintype "passive"))
      (node (ref "Q3") (pin "C") (pinfunction "C_C") (pintype "passive"))
      (node (ref "U$1") (pin "PAD3") (pinfunction "3_PAD3") (pintype "bidirectional"))
    )
    (net (code "39") (name "Net-(U$1-4)") (class "Default")
      (node (ref "Q3") (pin "B") (pinfunction "B_B") (pintype "passive"))
      (node (ref "U$1") (pin "PAD4") (pinfunction "4_PAD4") (pintype "bidirectional"))
    )
    (net (code "40") (name "Net-(U$1-6)") (class "Default")
      (node (ref "Q2") (pin "B") (pinfunction "B_B") (pintype "passive"))
      (node (ref "U$1") (pin "PAD6") (pinfunction "6_PAD6") (pintype "bidirectional"))
    )
    (net (code "41") (name "Net-(U$1-PIN8)") (class "Default")
      (node (ref "C7") (pin "1") (pinfunction "1_1") (pintype "passive"))
      (node (ref "U$1") (pin "PAD8") (pinfunction "PIN8_PAD8") (pintype "bidirectional"))
    )
    (net (code "42") (name "Net-(U$2-1)") (class "Default")
      (node (ref "C29") (pin "2") (pinfunction "2_2") (pintype "passive"))
      (node (ref "Q4") (pin "C") (pinfunction "C_C") (pintype "passive"))
      (node (ref "U$2") (pin "PAD1") (pinfunction "1_PAD1") (pintype "bidirectional"))
    )
    (net (code "43") (name "Net-(U$2-3)") (class "Default")
      (node (ref "C46") (pin "1") (pinfunction "1_1") (pintype "passive"))
      (node (ref "Q5") (pin "C") (pinfunction "C_C") (pintype "passive"))
      (node (ref "U$2") (pin "PAD3") (pinfunction "3_PAD3") (pintype "bidirectional"))
    )
    (net (code "44") (name "Net-(U$2-4)") (class "Default")
      (node (ref "Q5") (pin "B") (pinfunction "B_B") (pintype "passive"))
      (node (ref "U$2") (pin "PAD4") (pinfunction "4_PAD4") (pintype "bidirectional"))
    )
    (net (code "45") (name "Net-(U$2-6)") (class "Default")
      (node (ref "Q4") (pin "B") (pinfunction "B_B") (pintype "passive"))
      (node (ref "U$2") (pin "PAD6") (pinfunction "6_PAD6") (pintype "bidirectional"))
    )
    (net (code "46") (name "Net-(U$2-PIN8)") (class "Default")
      (node (ref "C30") (pin "1") (pinfunction "1_1") (pintype "passive"))
      (node (ref "U$2") (pin "PAD8") (pinfunction "PIN8_PAD8") (pintype "bidirectional"))
    )
    (net (code "47") (name "Net-(X1C-1)") (class "Default")
      (node (ref "SJ1") (pin "1") (pinfunction "1_1") (pintype "passive"))
      (node (ref "X1") (pin "GND@1") (pinfunction "1_GND@1") (pintype "passive"))
    )
    (net (code "48") (name "Net-(X1D-1)") (class "Default")
      (node (ref "SJ2") (pin "1") (pinfunction "1_1") (pintype "passive"))
      (node (ref "X1") (pin "GND@2") (pinfunction "1_GND@2") (pintype "passive"))
    )
    (net (code "49") (name "Net-(X1E-1)") (class "Default")
      (node (ref "SJ3") (pin "1") (pinfunction "1_1") (pintype "passive"))
      (node (ref "X1") (pin "GND@3") (pinfunction "1_GND@3") (pintype "passive"))
    )
    (net (code "50") (name "Net-(X1F-1)") (class "Default")
      (node (ref "SJ4") (pin "1") (pinfunction "1_1") (pintype "passive"))
      (node (ref "X1") (pin "GND@4") (pinfunction "1_GND@4") (pintype "passive"))
    )
    (net (code "51") (name "VBINA") (class "Default")
      (node (ref "R10") (pin "1") (pinfunction "1_1") (pintype "passive"))
      (node (ref "R11") (pin "2") (pinfunction "2_2") (pintype "passive"))
      (node (ref "U$1") (pin "PAD5") (pinfunction "5_PAD5") (pintype "bidirectional"))
    )
    (net (code "52") (name "VBINB") (class "Default")
      (node (ref "R26") (pin "1") (pinfunction "1_1") (pintype "passive"))
      (node (ref "R27") (pin "2") (pinfunction "2_2") (pintype "passive"))
      (node (ref "U$2") (pin "PAD5") (pinfunction "5_PAD5") (pintype "bidirectional"))
    )
    (net (code "53") (name "VH1A") (class "Default")
      (node (ref "C7") (pin "2") (pinfunction "2_2") (pintype "passive"))
      (node (ref "C9") (pin "1") (pinfunction "1_1") (pintype "passive"))
      (node (ref "D1") (pin "C") (pinfunction "C_C") (pintype "passive"))
      (node (ref "D2") (pin "A") (pinfunction "A_A") (pintype "passive"))
    )
    (net (code "54") (name "VH1B") (class "Default")
      (node (ref "C30") (pin "2") (pinfunction "2_2") (pintype "passive"))
      (node (ref "C32") (pin "1") (pinfunction "1_1") (pintype "passive"))
      (node (ref "D11") (pin "C") (pinfunction "C_C") (pintype "passive"))
      (node (ref "D14") (pin "A") (pinfunction "A_A") (pintype "passive"))
    )
    (net (code "55") (name "VH2A") (class "Default")
      (node (ref "C10") (pin "1") (pinfunction "1_1") (pintype "passive"))
      (node (ref "C8") (pin "2") (pinfunction "2_2") (pintype "passive"))
      (node (ref "D2") (pin "C") (pinfunction "C_C") (pintype "passive"))
      (node (ref "D3") (pin "A") (pinfunction "A_A") (pintype "passive"))
    )
    (net (code "56") (name "VH2B") (class "Default")
      (node (ref "C31") (pin "2") (pinfunction "2_2") (pintype "passive"))
      (node (ref "C33") (pin "1") (pinfunction "1_1") (pintype "passive"))
      (node (ref "D14") (pin "C") (pinfunction "C_C") (pintype "passive"))
      (node (ref "D15") (pin "A") (pinfunction "A_A") (pintype "passive"))
    )
    (net (code "57") (name "VH3A") (class "Default")
      (node (ref "C11") (pin "1") (pinfunction "1_1") (pintype "passive"))
      (node (ref "C9") (pin "2") (pinfunction "2_2") (pintype "passive"))
      (node (ref "D3") (pin "C") (pinfunction "C_C") (pintype "passive"))
      (node (ref "D4") (pin "A") (pinfunction "A_A") (pintype "passive"))
    )
    (net (code "58") (name "VH3B") (class "Default")
      (node (ref "C32") (pin "2") (pinfunction "2_2") (pintype "passive"))
      (node (ref "C34") (pin "1") (pinfunction "1_1") (pintype "passive"))
      (node (ref "D15") (pin "C") (pinfunction "C_C") (pintype "passive"))
      (node (ref "D16") (pin "A") (pinfunction "A_A") (pintype "passive"))
    )
    (net (code "59") (name "VH4A") (class "Default")
      (node (ref "C10") (pin "2") (pinfunction "2_2") (pintype "passive"))
      (node (ref "C12") (pin "1") (pinfunction "1_1") (pintype "passive"))
      (node (ref "D4") (pin "C") (pinfunction "C_C") (pintype "passive"))
      (node (ref "D5") (pin "A") (pinfunction "A_A") (pintype "passive"))
    )
    (net (code "60") (name "VH4B") (class "Default")
      (node (ref "C33") (pin "2") (pinfunction "2_2") (pintype "passive"))
      (node (ref "C35") (pin "1") (pinfunction "1_1") (pintype "passive"))
      (node (ref "D16") (pin "C") (pinfunction "C_C") (pintype "passive"))
      (node (ref "D17") (pin "A") (pinfunction "A_A") (pintype "passive"))
    )
    (net (code "61") (name "VH5A") (class "Default")
      (node (ref "C11") (pin "2") (pinfunction "2_2") (pintype "passive"))
      (node (ref "C13") (pin "1") (pinfunction "1_1") (pintype "passive"))
      (node (ref "D5") (pin "C") (pinfunction "C_C") (pintype "passive"))
      (node (ref "D6") (pin "A") (pinfunction "A_A") (pintype "passive"))
    )
    (net (code "62") (name "VH5B") (class "Default")
      (node (ref "C34") (pin "2") (pinfunction "2_2") (pintype "passive"))
      (node (ref "C36") (pin "1") (pinfunction "1_1") (pintype "passive"))
      (node (ref "D17") (pin "C") (pinfunction "C_C") (pintype "passive"))
      (node (ref "D18") (pin "A") (pinfunction "A_A") (pintype "passive"))
    )
    (net (code "63") (name "VH6A") (class "Default")
      (node (ref "C12") (pin "2") (pinfunction "2_2") (pintype "passive"))
      (node (ref "C15") (pin "1") (pinfunction "1_1") (pintype "passive"))
      (node (ref "D6") (pin "C") (pinfunction "C_C") (pintype "passive"))
      (node (ref "D7") (pin "A") (pinfunction "A_A") (pintype "passive"))
    )
    (net (code "64") (name "VH6B") (class "Default")
      (node (ref "C35") (pin "2") (pinfunction "2_2") (pintype "passive"))
      (node (ref "C37") (pin "1") (pinfunction "1_1") (pintype "passive"))
      (node (ref "D18") (pin "C") (pinfunction "C_C") (pintype "passive"))
      (node (ref "D19") (pin "A") (pinfunction "A_A") (pintype "passive"))
    )
    (net (code "65") (name "VH7A") (class "Default")
      (node (ref "C13") (pin "2") (pinfunction "2_2") (pintype "passive"))
      (node (ref "C16") (pin "1") (pinfunction "1_1") (pintype "passive"))
      (node (ref "D7") (pin "C") (pinfunction "C_C") (pintype "passive"))
      (node (ref "D8") (pin "A") (pinfunction "A_A") (pintype "passive"))
    )
    (net (code "66") (name "VH7B") (class "Default")
      (node (ref "C36") (pin "2") (pinfunction "2_2") (pintype "passive"))
      (node (ref "C38") (pin "1") (pinfunction "1_1") (pintype "passive"))
      (node (ref "D19") (pin "C") (pinfunction "C_C") (pintype "passive"))
      (node (ref "D20") (pin "A") (pinfunction "A_A") (pintype "passive"))
    )
    (net (code "67") (name "VH8A") (class "Default")
      (node (ref "C15") (pin "2") (pinfunction "2_2") (pintype "passive"))
      (node (ref "C17") (pin "1") (pinfunction "1_1") (pintype "passive"))
      (node (ref "D8") (pin "C") (pinfunction "C_C") (pintype "passive"))
      (node (ref "D9") (pin "A") (pinfunction "A_A") (pintype "passive"))
    )
    (net (code "68") (name "VH8B") (class "Default")
      (node (ref "C37") (pin "2") (pinfunction "2_2") (pintype "passive"))
      (node (ref "C39") (pin "1") (pinfunction "1_1") (pintype "passive"))
      (node (ref "D20") (pin "C") (pinfunction "C_C") (pintype "passive"))
      (node (ref "D21") (pin "A") (pinfunction "A_A") (pintype "passive"))
    )
    (net (code "69") (name "VH9A") (class "Default")
      (node (ref "C16") (pin "2") (pinfunction "2_2") (pintype "passive"))
      (node (ref "C18") (pin "1") (pinfunction "1_1") (pintype "passive"))
      (node (ref "D10") (pin "A") (pinfunction "A_A") (pintype "passive"))
      (node (ref "D9") (pin "C") (pinfunction "C_C") (pintype "passive"))
      (node (ref "R12") (pin "1") (pinfunction "1_1") (pintype "passive"))
    )
    (net (code "70") (name "VH9B") (class "Default")
      (node (ref "C38") (pin "2") (pinfunction "2_2") (pintype "passive"))
      (node (ref "C40") (pin "1") (pinfunction "1_1") (pintype "passive"))
      (node (ref "D21") (pin "C") (pinfunction "C_C") (pintype "passive"))
      (node (ref "D22") (pin "A") (pinfunction "A_A") (pintype "passive"))
      (node (ref "R28") (pin "1") (pinfunction "1_1") (pintype "passive"))
    )
    (net (code "71") (name "VH10A") (class "Default")
      (node (ref "C17") (pin "2") (pinfunction "2_2") (pintype "passive"))
      (node (ref "D10") (pin "C") (pinfunction "C_C") (pintype "passive"))
      (node (ref "D12") (pin "A") (pinfunction "A_A") (pintype "passive"))
    )
    (net (code "72") (name "VH10B") (class "Default")
      (node (ref "C39") (pin "2") (pinfunction "2_2") (pintype "passive"))
      (node (ref "D22") (pin "C") (pinfunction "C_C") (pintype "passive"))
      (node (ref "D23") (pin "A") (pinfunction "A_A") (pintype "passive"))
    )
    (net (code "73") (name "VH11") (class "Default")
      (node (ref "C40") (pin "2") (pinfunction "2_2") (pintype "passive"))
      (node (ref "D23") (pin "C") (pinfunction "C_C") (pintype "passive"))
    )
    (net (code "74") (name "VH11A") (class "Default")
      (node (ref "C18") (pin "2") (pinfunction "2_2") (pintype "passive"))
      (node (ref "D12") (pin "C") (pinfunction "C_C") (pintype "passive"))
    )
    (net (code "75") (name "VREFA") (class "Default")
      (node (ref "IC3") (pin "5") (pinfunction "+IN_5") (pintype "input"))
      (node (ref "R1") (pin "1") (pinfunction "1_1") (pintype "passive"))
      (node (ref "U1") (pin "1") (pinfunction "V+_1") (pintype "bidirectional"))
    )
    (net (code "76") (name "VREFB") (class "Default")
      (node (ref "IC1") (pin "5") (pinfunction "+IN_5") (pintype "input"))
      (node (ref "R17") (pin "1") (pinfunction "1_1") (pintype "passive"))
      (node (ref "U2") (pin "1") (pinfunction "V+_1") (pintype "bidirectional"))
    )
    (net (code "77") (name "VTINA") (class "Default")
      (node (ref "L1") (pin "P$2") (pinfunction "P$2_P$2") (pintype "passive"))
      (node (ref "U$1") (pin "PAD2") (pinfunction "2_PAD2") (pintype "bidirectional"))
    )
    (net (code "78") (name "VTINB") (class "Default")
      (node (ref "L2") (pin "P$2") (pinfunction "P$2_P$2") (pintype "passive"))
      (node (ref "U$2") (pin "PAD2") (pinfunction "2_PAD2") (pintype "bidirectional"))
    )
    (net (code "79") (name "unconnected-(U1-TRIM-Pad3)") (class "Default")
      (node (ref "U1") (pin "3") (pinfunction "TRIM_3") (pintype "bidirectional"))
    )
    (net (code "80") (name "unconnected-(U2-TRIM-Pad3)") (class "Default")
      (node (ref "U2") (pin "3") (pinfunction "TRIM_3") (pintype "bidirectional"))
    )
    (net (code "81") (name "unconnected-(X1A-+5V-PadB3)") (class "Default")
      (node (ref "X1") (pin "B3") (pinfunction "+5V_B3") (pintype "passive"))
    )
    (net (code "82") (name "unconnected-(X1A-+5V-PadB29)") (class "Default")
      (node (ref "X1") (pin "B29") (pinfunction "+5V_B29") (pintype "passive"))
    )
    (net (code "83") (name "unconnected-(X1A--5V-PadB5)") (class "Default")
      (node (ref "X1") (pin "B5") (pinfunction "-5V_B5") (pintype "passive"))
    )
    (net (code "84") (name "unconnected-(X1A--12V-PadB7)") (class "Default")
      (node (ref "X1") (pin "B7") (pinfunction "-12V_B7") (pintype "passive"))
    )
    (net (code "85") (name "unconnected-(X1A-AEN-PadA11)") (class "Default")
      (node (ref "X1") (pin "A11") (pinfunction "AEN_A11") (pintype "passive"))
    )
    (net (code "86") (name "unconnected-(X1A-BALE-PadB28)") (class "Default")
      (node (ref "X1") (pin "B28") (pinfunction "BALE_B28") (pintype "passive"))
    )
    (net (code "87") (name "unconnected-(X1A-DACK1-PadB17)") (class "Default")
      (node (ref "X1") (pin "B17") (pinfunction "DACK1_B17") (pintype "passive"))
    )
    (net (code "88") (name "unconnected-(X1A-DACK2-PadB26)") (class "Default")
      (node (ref "X1") (pin "B26") (pinfunction "DACK2_B26") (pintype "passive"))
    )
    (net (code "89") (name "unconnected-(X1A-DACK3-PadB15)") (class "Default")
      (node (ref "X1") (pin "B15") (pinfunction "DACK3_B15") (pintype "passive"))
    )
    (net (code "90") (name "unconnected-(X1A-DRQ1-PadB18)") (class "Default")
      (node (ref "X1") (pin "B18") (pinfunction "DRQ1_B18") (pintype "passive"))
    )
    (net (code "91") (name "unconnected-(X1A-DRQ2-PadB6)") (class "Default")
      (node (ref "X1") (pin "B6") (pinfunction "DRQ2_B6") (pintype "passive"))
    )
    (net (code "92") (name "unconnected-(X1A-DRQ3-PadB16)") (class "Default")
      (node (ref "X1") (pin "B16") (pinfunction "DRQ3_B16") (pintype "passive"))
    )
    (net (code "93") (name "unconnected-(X1A-ENDXFR-PadB8)") (class "Default")
      (node (ref "X1") (pin "B8") (pinfunction "ENDXFR_B8") (pintype "passive"))
    )
    (net (code "94") (name "unconnected-(X1A-IOCHCHK-PadA1)") (class "Default")
      (node (ref "X1") (pin "A1") (pinfunction "IOCHCHK_A1") (pintype "passive"))
    )
    (net (code "95") (name "unconnected-(X1A-IOCHRDY-PadA10)") (class "Default")
      (node (ref "X1") (pin "A10") (pinfunction "IOCHRDY_A10") (pintype "passive"))
    )
    (net (code "96") (name "unconnected-(X1A-IOR-PadB14)") (class "Default")
      (node (ref "X1") (pin "B14") (pinfunction "IOR_B14") (pintype "passive"))
    )
    (net (code "97") (name "unconnected-(X1A-IOW-PadB13)") (class "Default")
      (node (ref "X1") (pin "B13") (pinfunction "IOW_B13") (pintype "passive"))
    )
    (net (code "98") (name "unconnected-(X1A-IRQ3-PadB25)") (class "Default")
      (node (ref "X1") (pin "B25") (pinfunction "IRQ3_B25") (pintype "passive"))
    )
    (net (code "99") (name "unconnected-(X1A-IRQ4-PadB24)") (class "Default")
      (node (ref "X1") (pin "B24") (pinfunction "IRQ4_B24") (pintype "passive"))
    )
    (net (code "100") (name "unconnected-(X1A-IRQ5-PadB23)") (class "Default")
      (node (ref "X1") (pin "B23") (pinfunction "IRQ5_B23") (pintype "passive"))
    )
    (net (code "101") (name "unconnected-(X1A-IRQ6-PadB22)") (class "Default")
      (node (ref "X1") (pin "B22") (pinfunction "IRQ6_B22") (pintype "passive"))
    )
    (net (code "102") (name "unconnected-(X1A-IRQ7-PadB21)") (class "Default")
      (node (ref "X1") (pin "B21") (pinfunction "IRQ7_B21") (pintype "passive"))
    )
    (net (code "103") (name "unconnected-(X1A-IRQ9-PadB4)") (class "Default")
      (node (ref "X1") (pin "B4") (pinfunction "IRQ9_B4") (pintype "passive"))
    )
    (net (code "104") (name "unconnected-(X1A-KEY-PadB10)") (class "Default")
      (node (ref "X1") (pin "B10") (pinfunction "KEY_B10") (pintype "passive"))
    )
    (net (code "105") (name "unconnected-(X1A-OSC-PadB30)") (class "Default")
      (node (ref "X1") (pin "B30") (pinfunction "OSC_B30") (pintype "passive"))
    )
    (net (code "106") (name "unconnected-(X1A-REFRESH-PadB19)") (class "Default")
      (node (ref "X1") (pin "B19") (pinfunction "REFRESH_B19") (pintype "passive"))
    )
    (net (code "107") (name "unconnected-(X1A-RESETDRV-PadB2)") (class "Default")
      (node (ref "X1") (pin "B2") (pinfunction "RESETDRV_B2") (pintype "passive"))
    )
    (net (code "108") (name "unconnected-(X1A-SA0-PadA31)") (class "Default")
      (node (ref "X1") (pin "A31") (pinfunction "SA0_A31") (pintype "passive"))
    )
    (net (code "109") (name "unconnected-(X1A-SA1-PadA30)") (class "Default")
      (node (ref "X1") (pin "A30") (pinfunction "SA1_A30") (pintype "passive"))
    )
    (net (code "110") (name "unconnected-(X1A-SA2-PadA29)") (class "Default")
      (node (ref "X1") (pin "A29") (pinfunction "SA2_A29") (pintype "passive"))
    )
    (net (code "111") (name "unconnected-(X1A-SA3-PadA28)") (class "Default")
      (node (ref "X1") (pin "A28") (pinfunction "SA3_A28") (pintype "passive"))
    )
    (net (code "112") (name "unconnected-(X1A-SA4-PadA27)") (class "Default")
      (node (ref "X1") (pin "A27") (pinfunction "SA4_A27") (pintype "passive"))
    )
    (net (code "113") (name "unconnected-(X1A-SA5-PadA26)") (class "Default")
      (node (ref "X1") (pin "A26") (pinfunction "SA5_A26") (pintype "passive"))
    )
    (net (code "114") (name "unconnected-(X1A-SA6-PadA25)") (class "Default")
      (node (ref "X1") (pin "A25") (pinfunction "SA6_A25") (pintype "passive"))
    )
    (net (code "115") (name "unconnected-(X1A-SA7-PadA24)") (class "Default")
      (node (ref "X1") (pin "A24") (pinfunction "SA7_A24") (pintype "passive"))
    )
    (net (code "116") (name "unconnected-(X1A-SA8-PadA23)") (class "Default")
      (node (ref "X1") (pin "A23") (pinfunction "SA8_A23") (pintype "passive"))
    )
    (net (code "117") (name "unconnected-(X1A-SA9-PadA22)") (class "Default")
      (node (ref "X1") (pin "A22") (pinfunction "SA9_A22") (pintype "passive"))
    )
    (net (code "118") (name "unconnected-(X1A-SA10-PadA21)") (class "Default")
      (node (ref "X1") (pin "A21") (pinfunction "SA10_A21") (pintype "passive"))
    )
    (net (code "119") (name "unconnected-(X1A-SA11-PadA20)") (class "Default")
      (node (ref "X1") (pin "A20") (pinfunction "SA11_A20") (pintype "passive"))
    )
    (net (code "120") (name "unconnected-(X1A-SA12-PadA19)") (class "Default")
      (node (ref "X1") (pin "A19") (pinfunction "SA12_A19") (pintype "passive"))
    )
    (net (code "121") (name "unconnected-(X1A-SA13-PadA18)") (class "Default")
      (node (ref "X1") (pin "A18") (pinfunction "SA13_A18") (pintype "passive"))
    )
    (net (code "122") (name "unconnected-(X1A-SA14-PadA17)") (class "Default")
      (node (ref "X1") (pin "A17") (pinfunction "SA14_A17") (pintype "passive"))
    )
    (net (code "123") (name "unconnected-(X1A-SA15-PadA16)") (class "Default")
      (node (ref "X1") (pin "A16") (pinfunction "SA15_A16") (pintype "passive"))
    )
    (net (code "124") (name "unconnected-(X1A-SA16-PadA15)") (class "Default")
      (node (ref "X1") (pin "A15") (pinfunction "SA16_A15") (pintype "passive"))
    )
    (net (code "125") (name "unconnected-(X1A-SA17-PadA14)") (class "Default")
      (node (ref "X1") (pin "A14") (pinfunction "SA17_A14") (pintype "passive"))
    )
    (net (code "126") (name "unconnected-(X1A-SA18-PadA13)") (class "Default")
      (node (ref "X1") (pin "A13") (pinfunction "SA18_A13") (pintype "passive"))
    )
    (net (code "127") (name "unconnected-(X1A-SA19-PadA12)") (class "Default")
      (node (ref "X1") (pin "A12") (pinfunction "SA19_A12") (pintype "passive"))
    )
    (net (code "128") (name "unconnected-(X1A-SD0-PadA9)") (class "Default")
      (node (ref "X1") (pin "A9") (pinfunction "SD0_A9") (pintype "passive"))
    )
    (net (code "129") (name "unconnected-(X1A-SD1-PadA8)") (class "Default")
      (node (ref "X1") (pin "A8") (pinfunction "SD1_A8") (pintype "passive"))
    )
    (net (code "130") (name "unconnected-(X1A-SD2-PadA7)") (class "Default")
      (node (ref "X1") (pin "A7") (pinfunction "SD2_A7") (pintype "passive"))
    )
    (net (code "131") (name "unconnected-(X1A-SD3-PadA6)") (class "Default")
      (node (ref "X1") (pin "A6") (pinfunction "SD3_A6") (pintype "passive"))
    )
    (net (code "132") (name "unconnected-(X1A-SD4-PadA5)") (class "Default")
      (node (ref "X1") (pin "A5") (pinfunction "SD4_A5") (pintype "passive"))
    )
    (net (code "133") (name "unconnected-(X1A-SD5-PadA4)") (class "Default")
      (node (ref "X1") (pin "A4") (pinfunction "SD5_A4") (pintype "passive"))
    )
    (net (code "134") (name "unconnected-(X1A-SD6-PadA3)") (class "Default")
      (node (ref "X1") (pin "A3") (pinfunction "SD6_A3") (pintype "passive"))
    )
    (net (code "135") (name "unconnected-(X1A-SD7-PadA2)") (class "Default")
      (node (ref "X1") (pin "A2") (pinfunction "SD7_A2") (pintype "passive"))
    )
    (net (code "136") (name "unconnected-(X1A-SMEMR-PadB12)") (class "Default")
      (node (ref "X1") (pin "B12") (pinfunction "SMEMR_B12") (pintype "passive"))
    )
    (net (code "137") (name "unconnected-(X1A-SMEMW-PadB11)") (class "Default")
      (node (ref "X1") (pin "B11") (pinfunction "SMEMW_B11") (pintype "passive"))
    )
    (net (code "138") (name "unconnected-(X1A-SYSCLK-PadB20)") (class "Default")
      (node (ref "X1") (pin "B20") (pinfunction "SYSCLK_B20") (pintype "passive"))
    )
    (net (code "139") (name "unconnected-(X1A-TC-PadB27)") (class "Default")
      (node (ref "X1") (pin "B27") (pinfunction "TC_B27") (pintype "passive"))
    )
    (net (code "140") (name "unconnected-(X1B-+5V-PadD16)") (class "Default")
      (node (ref "X1") (pin "D16") (pinfunction "+5V_D16") (pintype "passive"))
    )
    (net (code "141") (name "unconnected-(X1B-DACK0-PadD8)") (class "Default")
      (node (ref "X1") (pin "D8") (pinfunction "DACK0_D8") (pintype "passive"))
    )
    (net (code "142") (name "unconnected-(X1B-DACK5-PadD10)") (class "Default")
      (node (ref "X1") (pin "D10") (pinfunction "DACK5_D10") (pintype "passive"))
    )
    (net (code "143") (name "unconnected-(X1B-DACK6-PadD12)") (class "Default")
      (node (ref "X1") (pin "D12") (pinfunction "DACK6_D12") (pintype "passive"))
    )
    (net (code "144") (name "unconnected-(X1B-DACK7-PadD14)") (class "Default")
      (node (ref "X1") (pin "D14") (pinfunction "DACK7_D14") (pintype "passive"))
    )
    (net (code "145") (name "unconnected-(X1B-DRQ0-PadD9)") (class "Default")
      (node (ref "X1") (pin "D9") (pinfunction "DRQ0_D9") (pintype "passive"))
    )
    (net (code "146") (name "unconnected-(X1B-DRQ5-PadD11)") (class "Default")
      (node (ref "X1") (pin "D11") (pinfunction "DRQ5_D11") (pintype "passive"))
    )
    (net (code "147") (name "unconnected-(X1B-DRQ6-PadD13)") (class "Default")
      (node (ref "X1") (pin "D13") (pinfunction "DRQ6_D13") (pintype "passive"))
    )
    (net (code "148") (name "unconnected-(X1B-DRQ7-PadD15)") (class "Default")
      (node (ref "X1") (pin "D15") (pinfunction "DRQ7_D15") (pintype "passive"))
    )
    (net (code "149") (name "unconnected-(X1B-IOCS16-PadD2)") (class "Default")
      (node (ref "X1") (pin "D2") (pinfunction "IOCS16_D2") (pintype "passive"))
    )
    (net (code "150") (name "unconnected-(X1B-IRQ10-PadD3)") (class "Default")
      (node (ref "X1") (pin "D3") (pinfunction "IRQ10_D3") (pintype "passive"))
    )
    (net (code "151") (name "unconnected-(X1B-IRQ11-PadD4)") (class "Default")
      (node (ref "X1") (pin "D4") (pinfunction "IRQ11_D4") (pintype "passive"))
    )
    (net (code "152") (name "unconnected-(X1B-IRQ12-PadD5)") (class "Default")
      (node (ref "X1") (pin "D5") (pinfunction "IRQ12_D5") (pintype "passive"))
    )
    (net (code "153") (name "unconnected-(X1B-IRQ14-PadD7)") (class "Default")
      (node (ref "X1") (pin "D7") (pinfunction "IRQ14_D7") (pintype "passive"))
    )
    (net (code "154") (name "unconnected-(X1B-IRQ15-PadD6)") (class "Default")
      (node (ref "X1") (pin "D6") (pinfunction "IRQ15_D6") (pintype "passive"))
    )
    (net (code "155") (name "unconnected-(X1B-KEY-PadC19)") (class "Default")
      (node (ref "X1") (pin "C19") (pinfunction "KEY_C19") (pintype "passive"))
    )
    (net (code "156") (name "unconnected-(X1B-LA17-PadC8)") (class "Default")
      (node (ref "X1") (pin "C8") (pinfunction "LA17_C8") (pintype "passive"))
    )
    (net (code "157") (name "unconnected-(X1B-LA18-PadC7)") (class "Default")
      (node (ref "X1") (pin "C7") (pinfunction "LA18_C7") (pintype "passive"))
    )
    (net (code "158") (name "unconnected-(X1B-LA19-PadC6)") (class "Default")
      (node (ref "X1") (pin "C6") (pinfunction "LA19_C6") (pintype "passive"))
    )
    (net (code "159") (name "unconnected-(X1B-LA20-PadC5)") (class "Default")
      (node (ref "X1") (pin "C5") (pinfunction "LA20_C5") (pintype "passive"))
    )
    (net (code "160") (name "unconnected-(X1B-LA21-PadC4)") (class "Default")
      (node (ref "X1") (pin "C4") (pinfunction "LA21_C4") (pintype "passive"))
    )
    (net (code "161") (name "unconnected-(X1B-LA22-PadC3)") (class "Default")
      (node (ref "X1") (pin "C3") (pinfunction "LA22_C3") (pintype "passive"))
    )
    (net (code "162") (name "unconnected-(X1B-LA23-PadC2)") (class "Default")
      (node (ref "X1") (pin "C2") (pinfunction "LA23_C2") (pintype "passive"))
    )
    (net (code "163") (name "unconnected-(X1B-MASTER-PadD17)") (class "Default")
      (node (ref "X1") (pin "D17") (pinfunction "MASTER_D17") (pintype "passive"))
    )
    (net (code "164") (name "unconnected-(X1B-MEMCS16-PadD1)") (class "Default")
      (node (ref "X1") (pin "D1") (pinfunction "MEMCS16_D1") (pintype "passive"))
    )
    (net (code "165") (name "unconnected-(X1B-MEMR-PadC9)") (class "Default")
      (node (ref "X1") (pin "C9") (pinfunction "MEMR_C9") (pintype "passive"))
    )
    (net (code "166") (name "unconnected-(X1B-MEMW-PadC10)") (class "Default")
      (node (ref "X1") (pin "C10") (pinfunction "MEMW_C10") (pintype "passive"))
    )
    (net (code "167") (name "unconnected-(X1B-SBHE-PadC1)") (class "Default")
      (node (ref "X1") (pin "C1") (pinfunction "SBHE_C1") (pintype "passive"))
    )
    (net (code "168") (name "unconnected-(X1B-SD8-PadC11)") (class "Default")
      (node (ref "X1") (pin "C11") (pinfunction "SD8_C11") (pintype "passive"))
    )
    (net (code "169") (name "unconnected-(X1B-SD9-PadC12)") (class "Default")
      (node (ref "X1") (pin "C12") (pinfunction "SD9_C12") (pintype "passive"))
    )
    (net (code "170") (name "unconnected-(X1B-SD10-PadC13)") (class "Default")
      (node (ref "X1") (pin "C13") (pinfunction "SD10_C13") (pintype "passive"))
    )
    (net (code "171") (name "unconnected-(X1B-SD11-PadC14)") (class "Default")
      (node (ref "X1") (pin "C14") (pinfunction "SD11_C14") (pintype "passive"))
    )
    (net (code "172") (name "unconnected-(X1B-SD12-PadC15)") (class "Default")
      (node (ref "X1") (pin "C15") (pinfunction "SD12_C15") (pintype "passive"))
    )
    (net (code "173") (name "unconnected-(X1B-SD13-PadC16)") (class "Default")
      (node (ref "X1") (pin "C16") (pinfunction "SD13_C16") (pintype "passive"))
    )
    (net (code "174") (name "unconnected-(X1B-SD14-PadC17)") (class "Default")
      (node (ref "X1") (pin "C17") (pinfunction "SD14_C17") (pintype "passive"))
    )
    (net (code "175") (name "unconnected-(X1B-SD15-PadC18)") (class "Default")
      (node (ref "X1") (pin "C18") (pinfunction "SD15_C18") (pintype "passive"))
    )
  )
)
